# 7DI_V2_R2.net
KiCad netlist of a schematic drawn in EAGLE
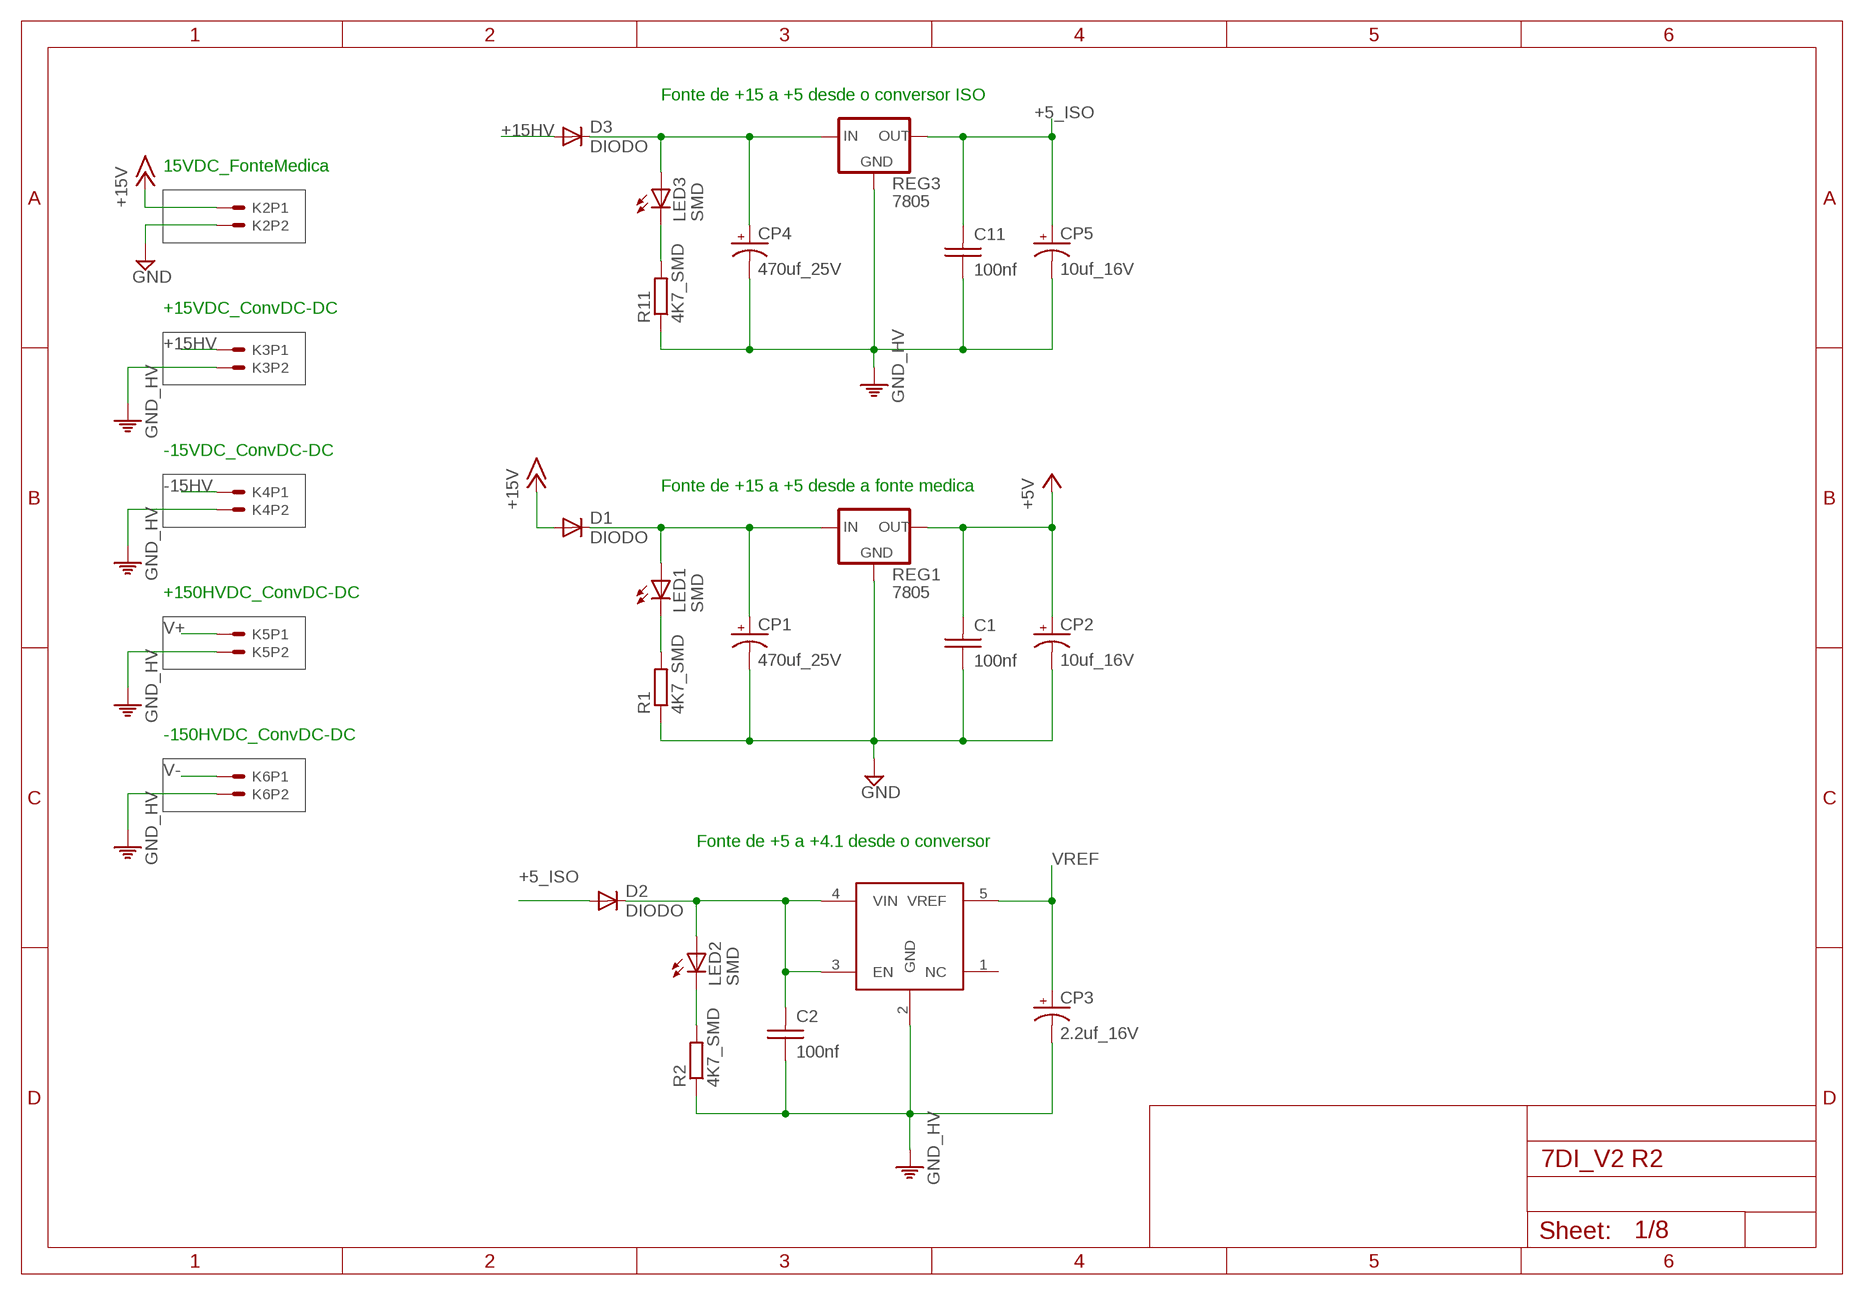
[diagram p0: schematic, sheet 1]
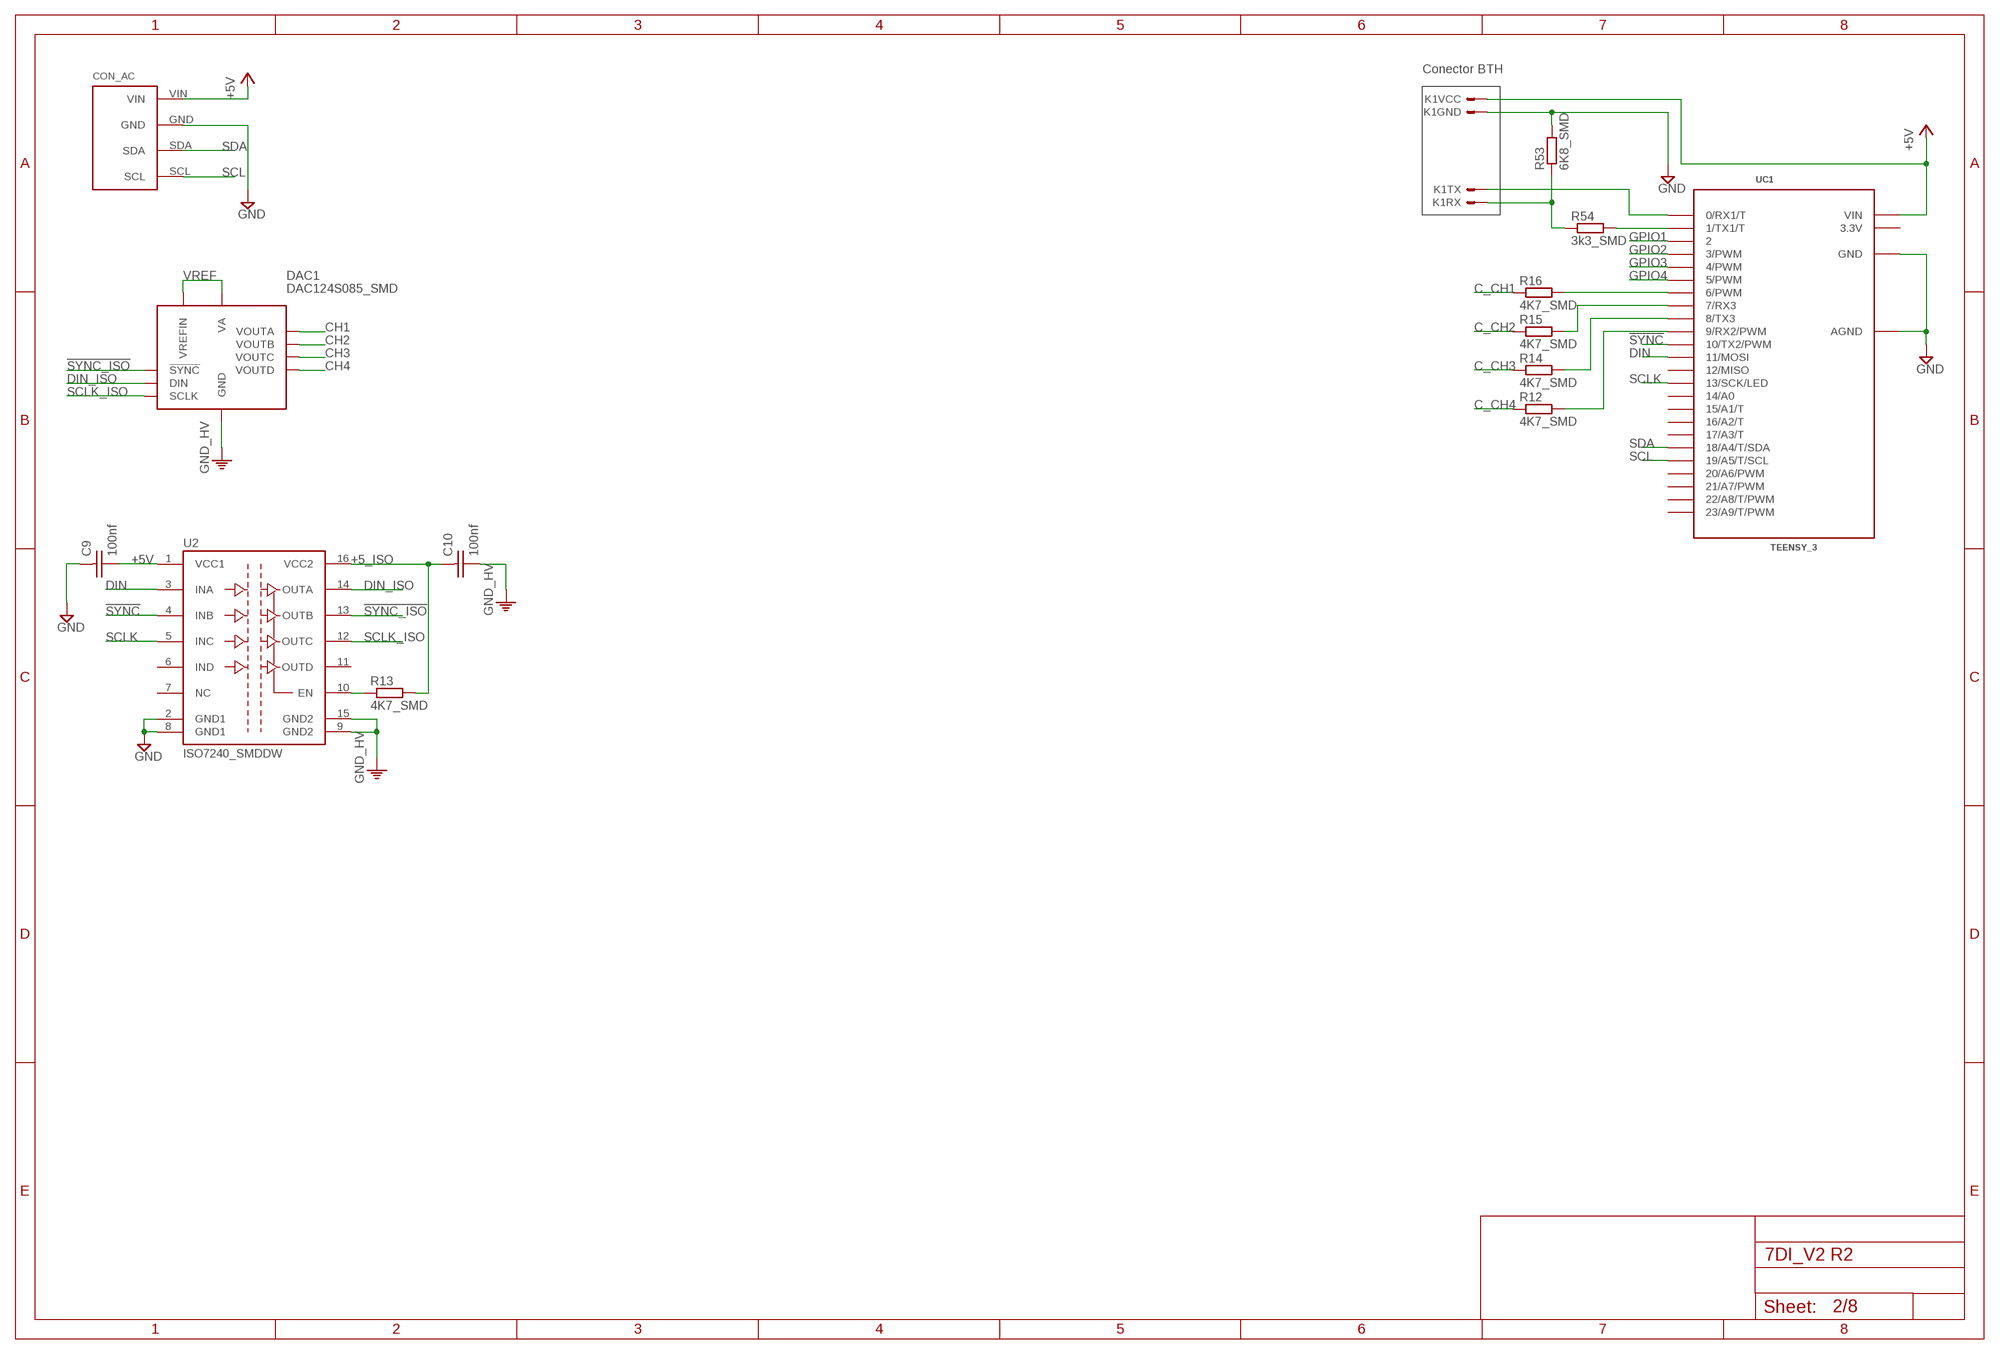
[diagram p1: schematic, sheet 2]
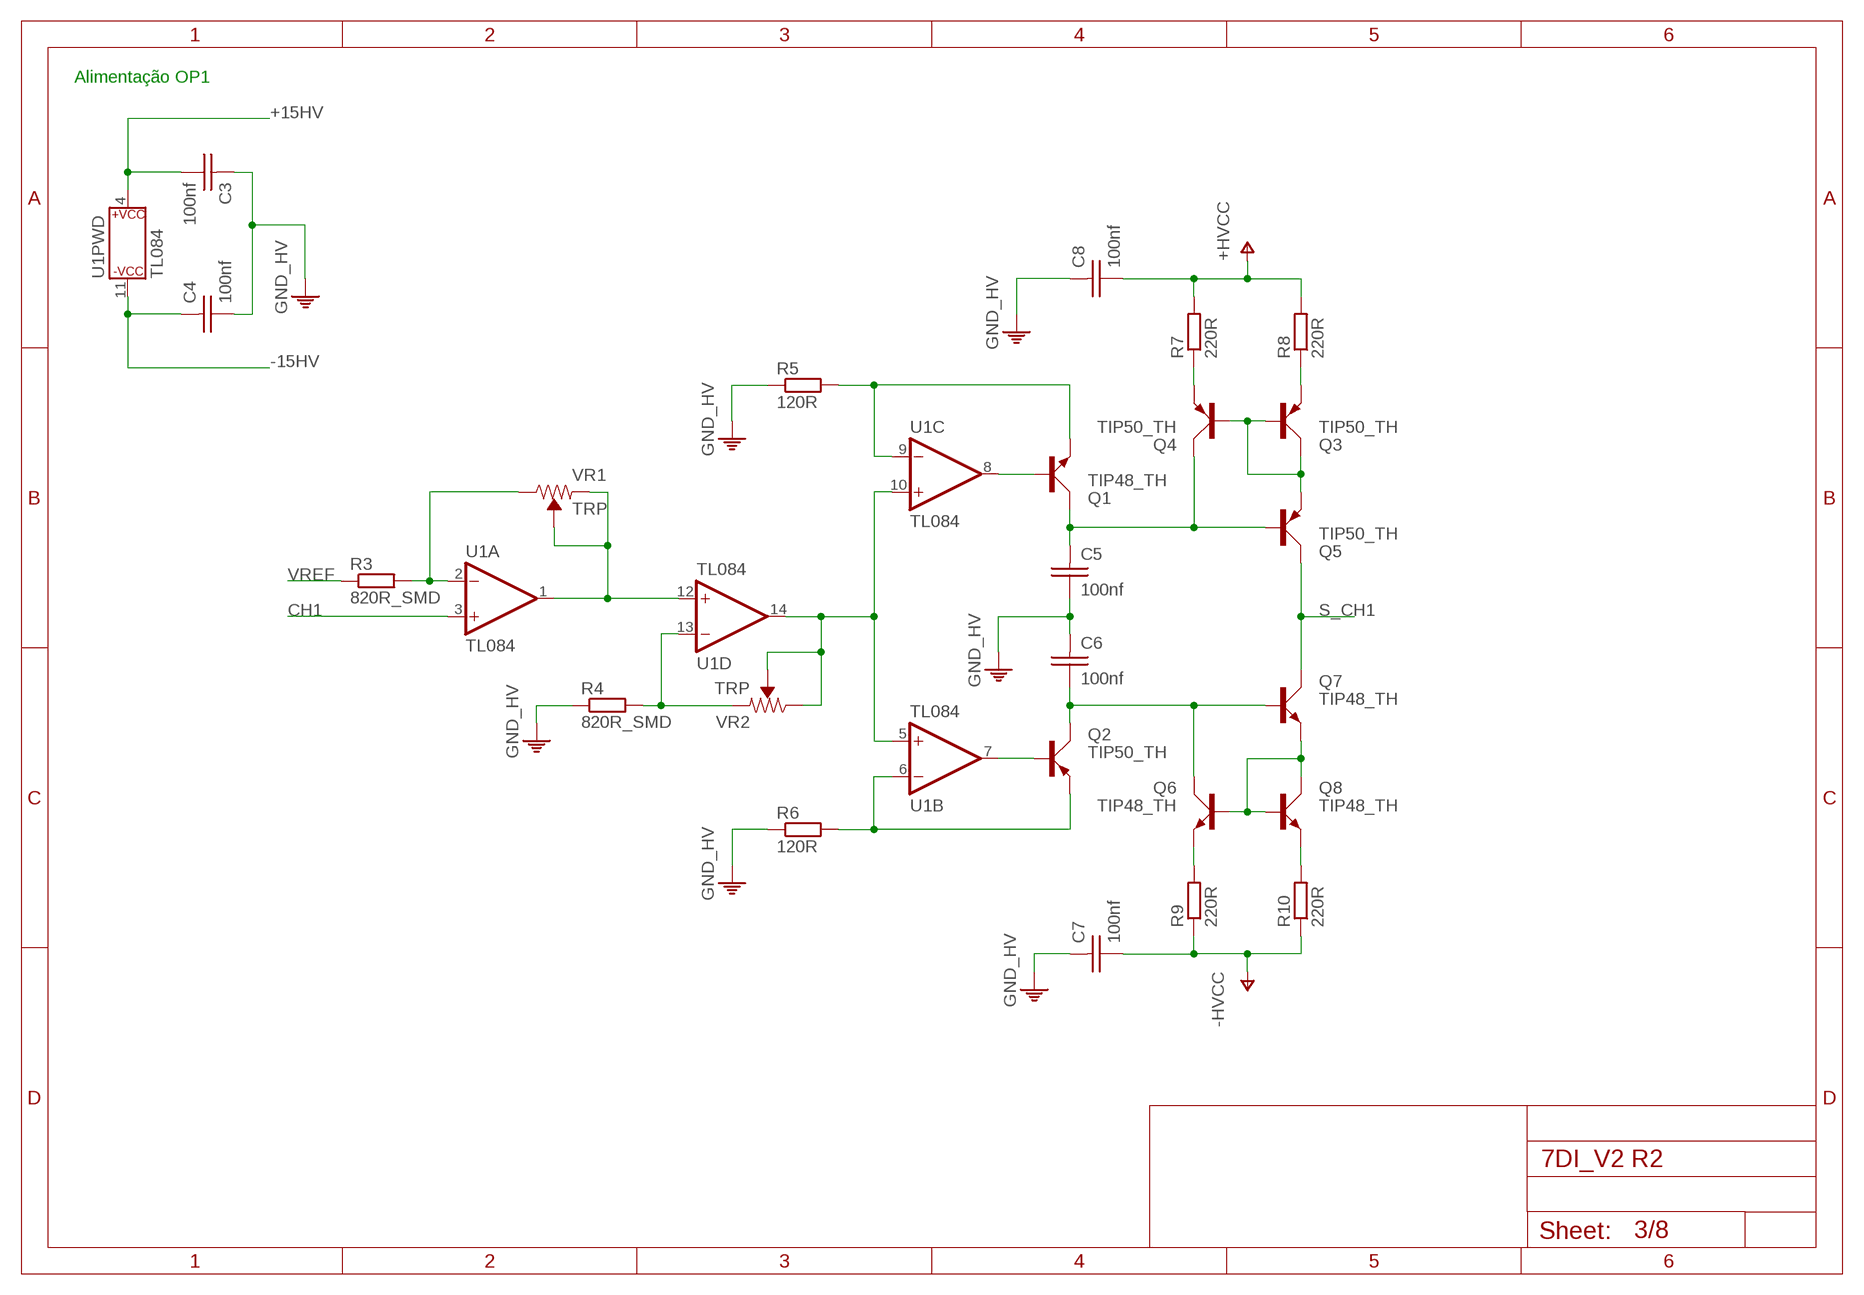
[diagram p2: schematic, sheet 3]
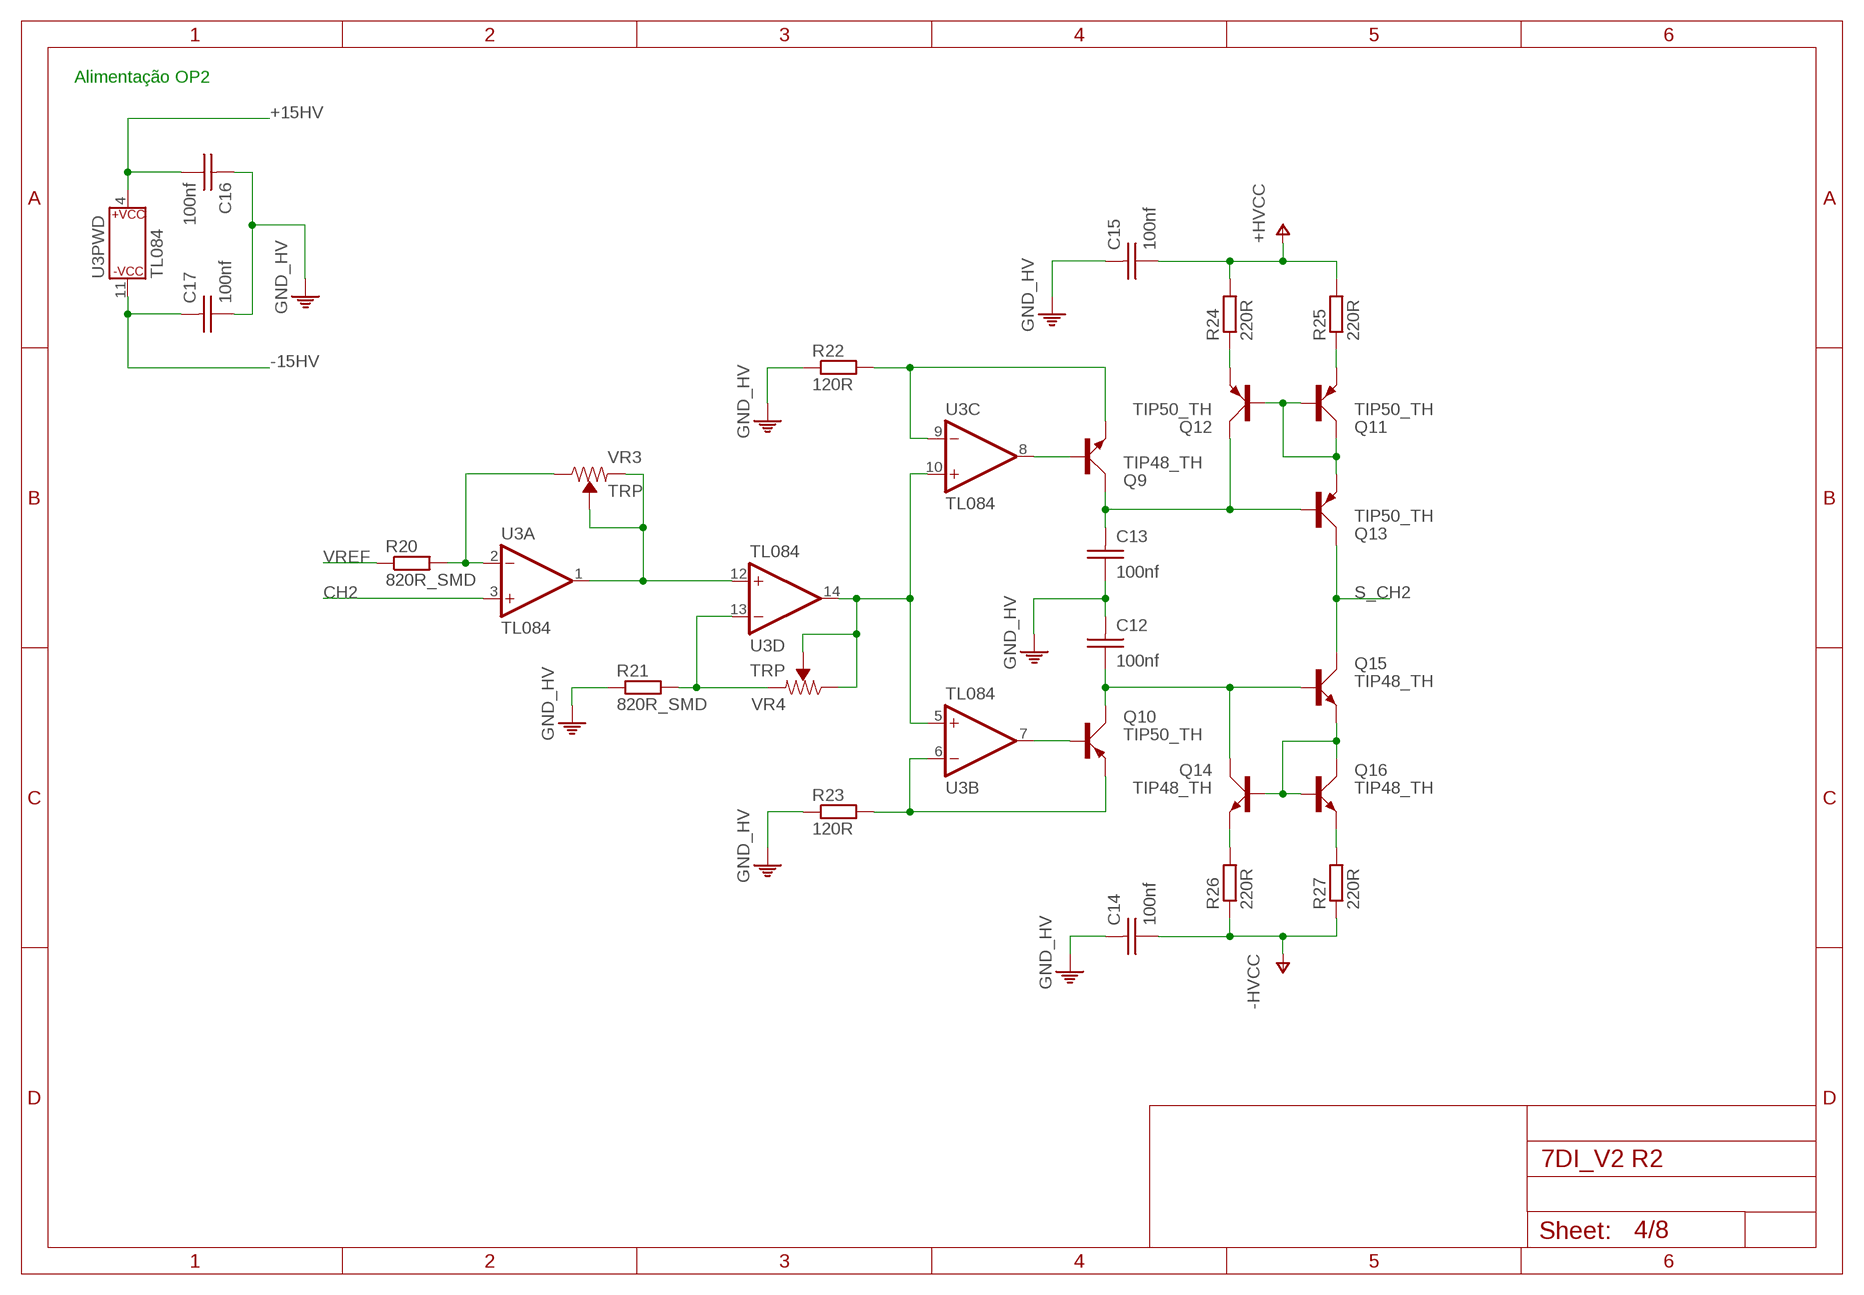
[diagram p3: schematic, sheet 4]
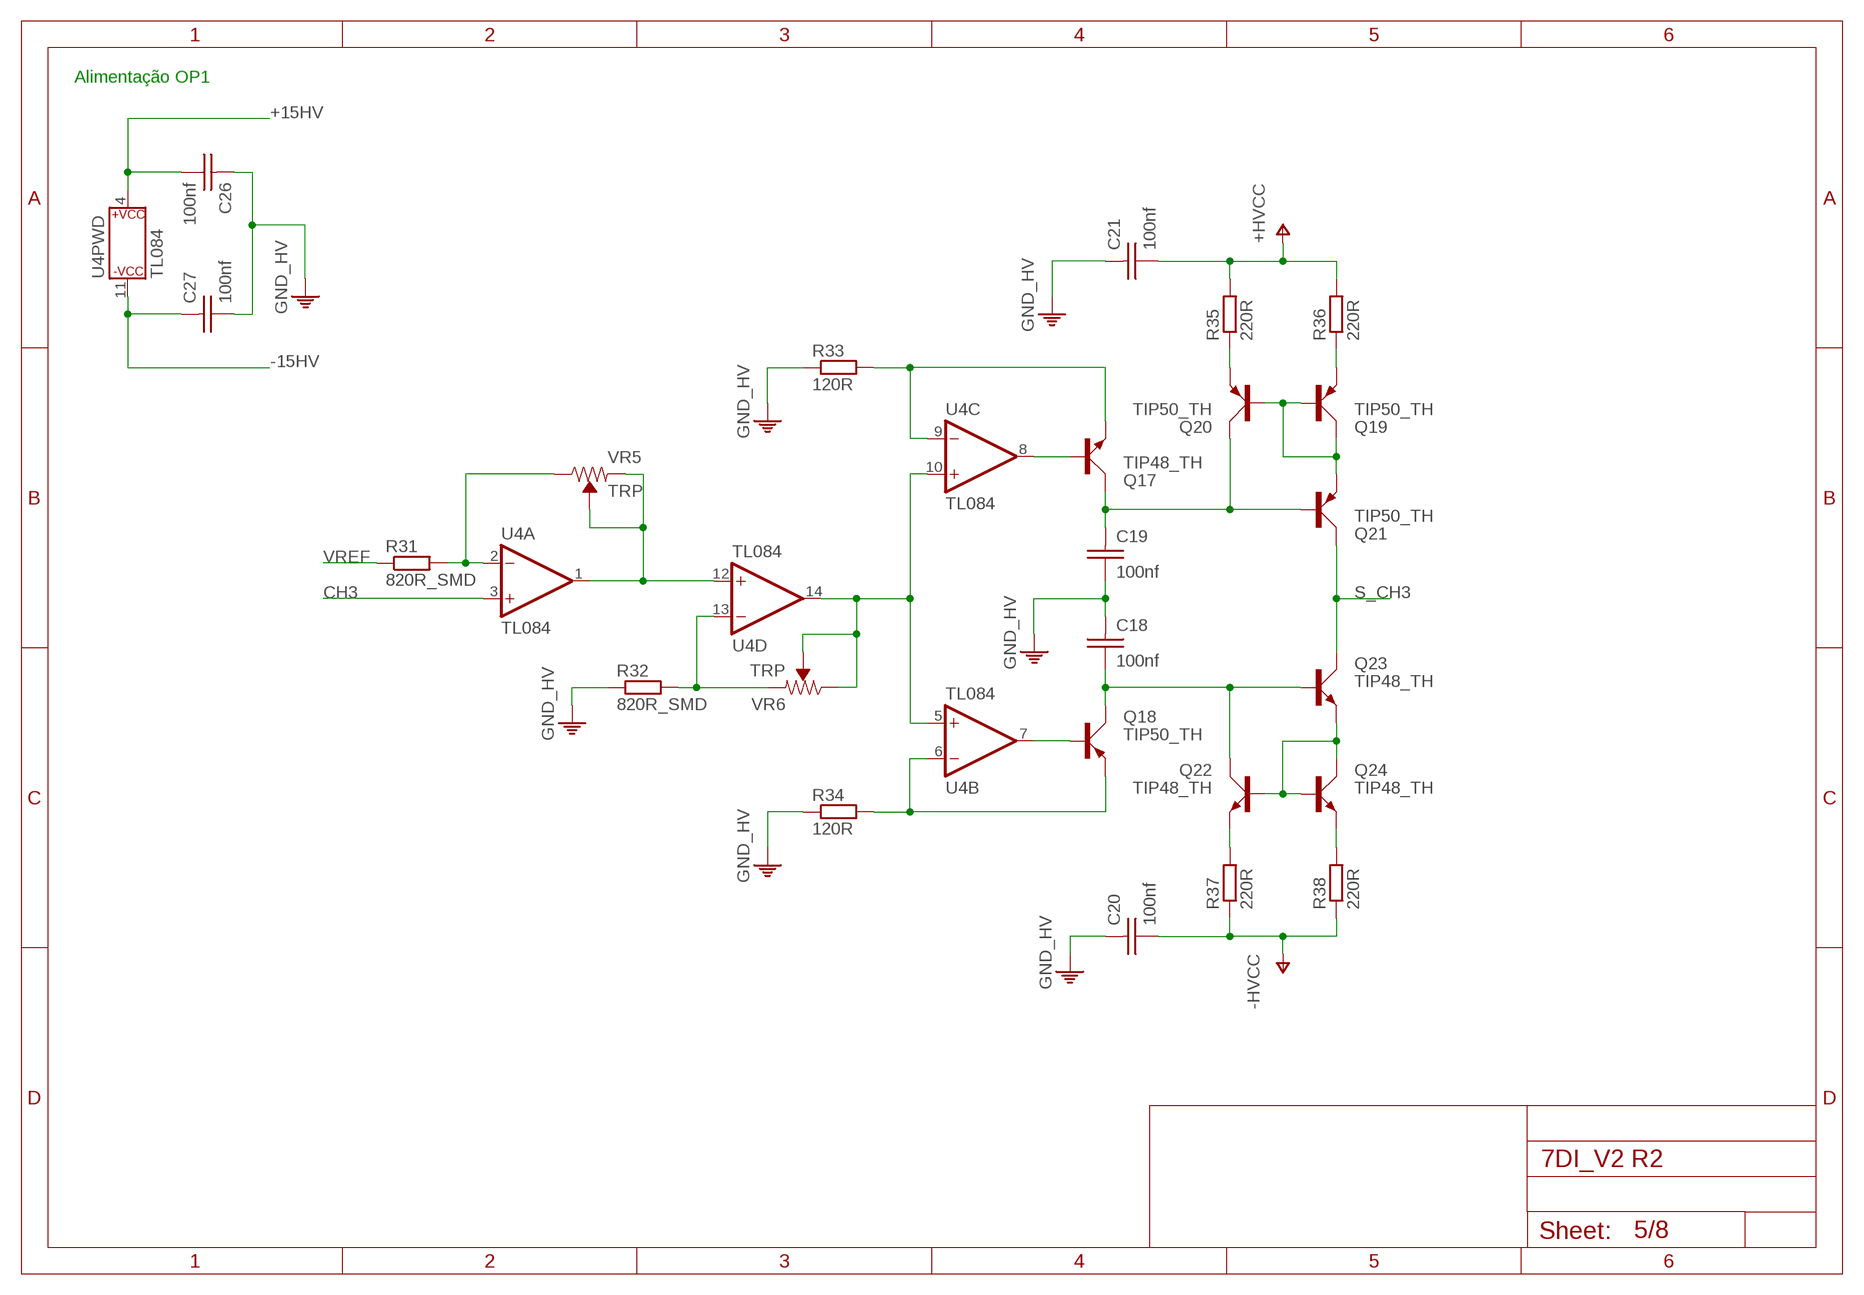
[diagram p4: schematic, sheet 5]
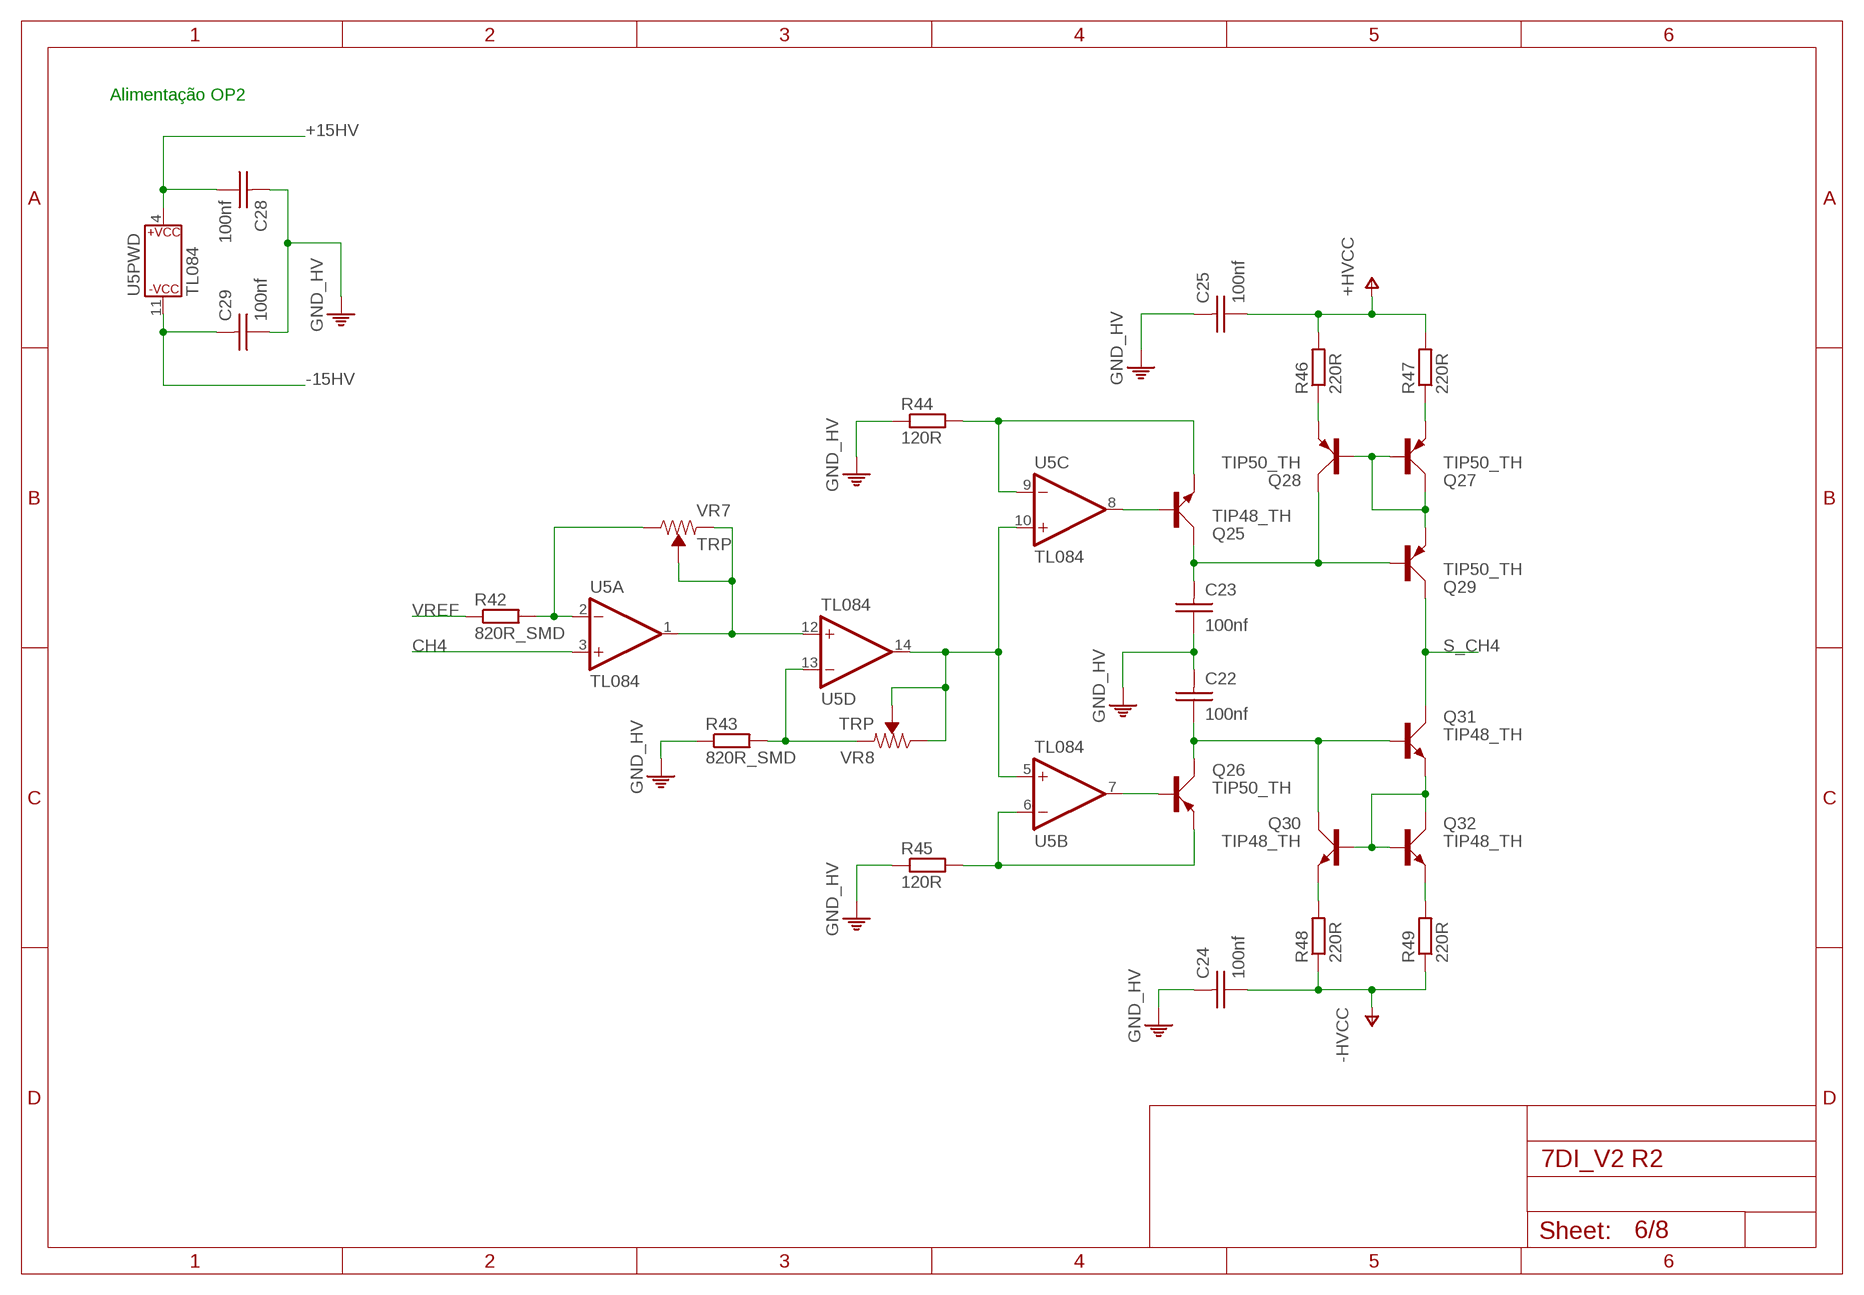
[diagram p5: schematic, sheet 6]
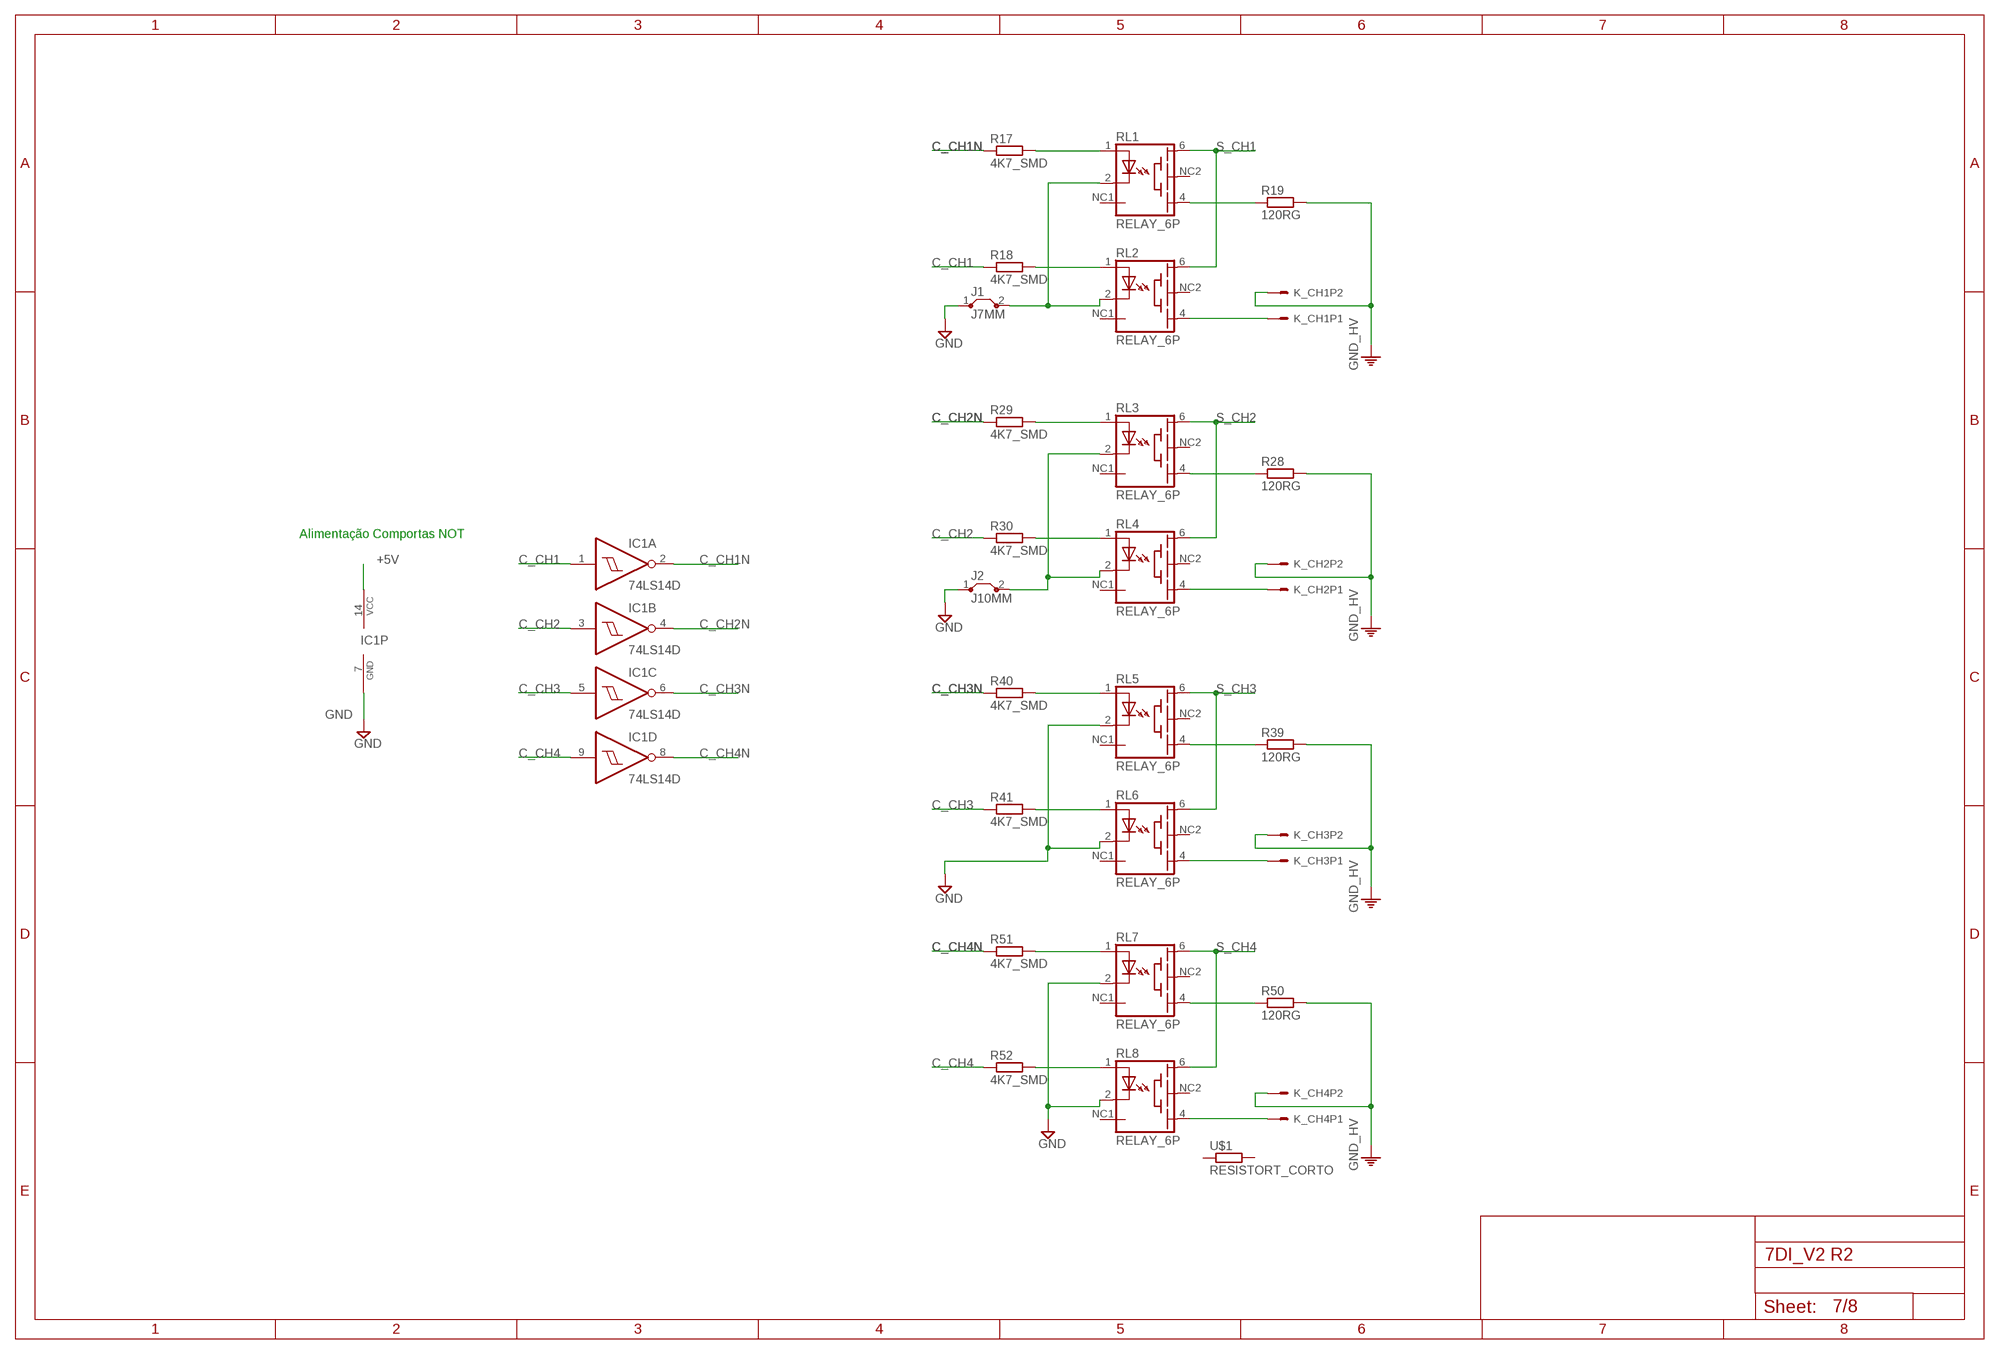
[diagram p6: schematic, sheet 7]
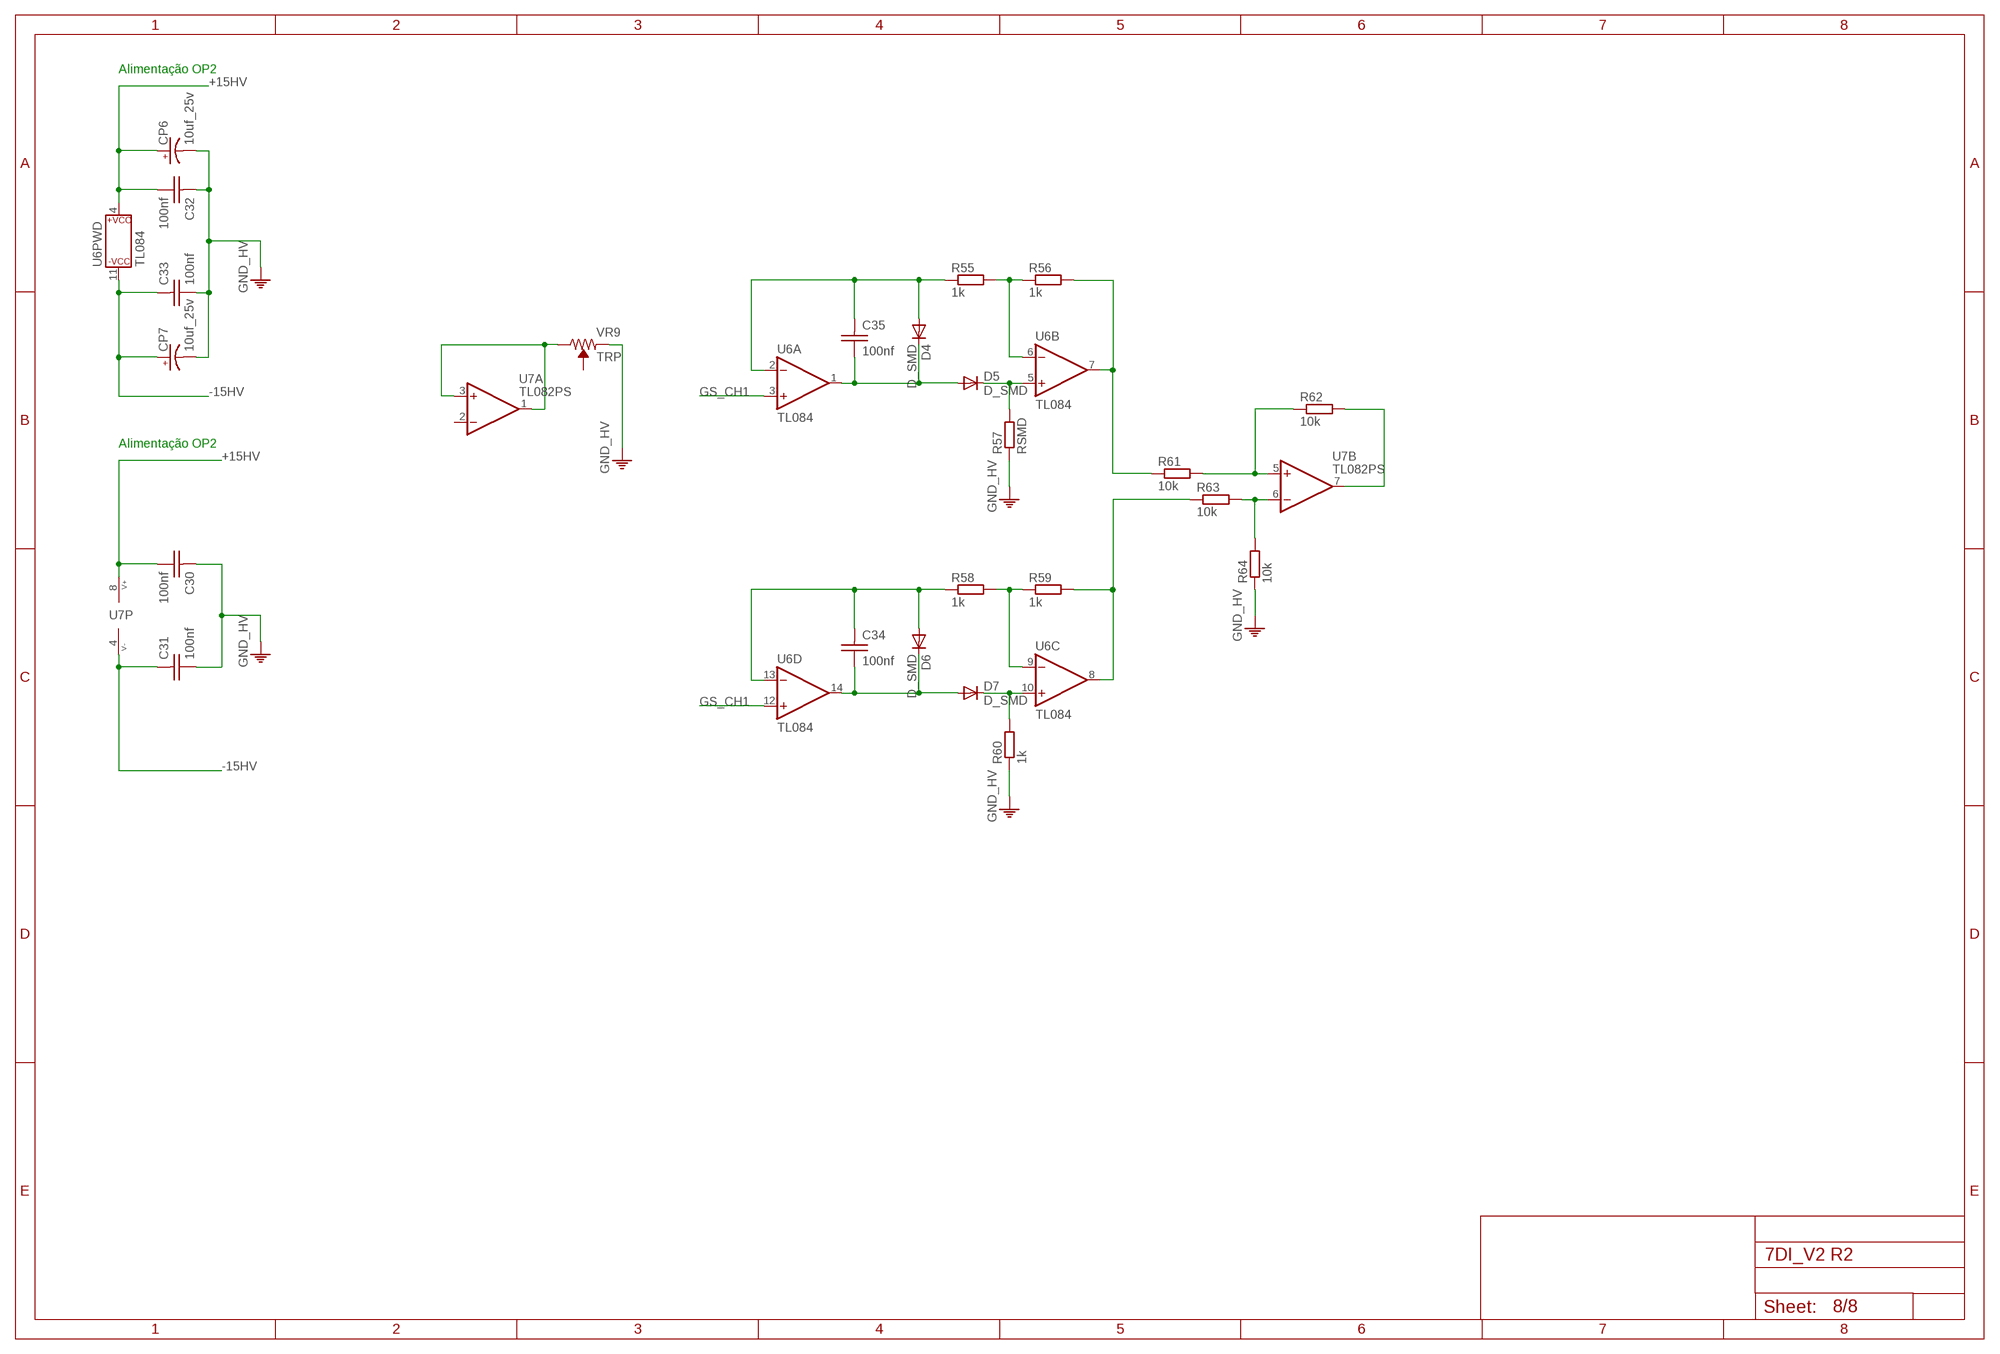
[diagram p7: schematic, sheet 8]

(export (version "E")
  (design (tool "Eeschema 10.0.6"))
  (components
    (comp (ref "C22")
      (value "100nf")
      (footprint "eagle-import:CAP_CER_2,54-5X5")
      (libsource (lib "eagle-import") (part "CAP_CERAMICO_TH2"))
    )
    (comp (ref "C23")
      (value "100nf")
      (footprint "eagle-import:CAP_CER_2,54-5X5")
      (libsource (lib "eagle-import") (part "CAP_CERAMICO_TH2"))
    )
    (comp (ref "C24")
      (value "100nf")
      (footprint "eagle-import:CAP_CER_16X7")
      (libsource (lib "eagle-import") (part "CAP_CERAMICO_TH16"))
    )
    (comp (ref "C25")
      (value "100nf")
      (footprint "eagle-import:CAP_CER_16X7")
      (libsource (lib "eagle-import") (part "CAP_CERAMICO_TH16"))
    )
    (comp (ref "C28")
      (value "100nf")
      (footprint "eagle-import:CAP_CER_SMD-0805")
      (libsource (lib "eagle-import") (part "CAP_CERAMICO_SMD"))
    )
    (comp (ref "C29")
      (value "100nf")
      (footprint "eagle-import:CAP_CER_SMD-0805")
      (libsource (lib "eagle-import") (part "CAP_CERAMICO_SMD"))
    )
    (comp (ref "Q25")
      (value "TIP48_TH")
      (footprint "eagle-import:TO220")
      (libsource (lib "eagle-import") (part "TIP48_TH"))
    )
    (comp (ref "Q26")
      (value "TIP50_TH")
      (footprint "eagle-import:TO220")
      (libsource (lib "eagle-import") (part "TIP50_TH"))
    )
    (comp (ref "Q27")
      (value "TIP50_TH")
      (footprint "eagle-import:TO220")
      (libsource (lib "eagle-import") (part "TIP50_TH"))
    )
    (comp (ref "Q28")
      (value "TIP50_TH")
      (footprint "eagle-import:TO220")
      (libsource (lib "eagle-import") (part "TIP50_TH"))
    )
    (comp (ref "Q29")
      (value "TIP50_TH")
      (footprint "eagle-import:TO220")
      (libsource (lib "eagle-import") (part "TIP50_TH"))
    )
    (comp (ref "Q30")
      (value "TIP48_TH")
      (footprint "eagle-import:TO220")
      (libsource (lib "eagle-import") (part "TIP48_TH"))
    )
    (comp (ref "Q31")
      (value "TIP48_TH")
      (footprint "eagle-import:TO220")
      (libsource (lib "eagle-import") (part "TIP48_TH"))
    )
    (comp (ref "Q32")
      (value "TIP48_TH")
      (footprint "eagle-import:TO220")
      (libsource (lib "eagle-import") (part "TIP48_TH"))
    )
    (comp (ref "R42")
      (value "820R_SMD")
      (footprint "eagle-import:RESISTENCIA_0805")
      (libsource (lib "eagle-import") (part "RESISTORSMD_0805"))
    )
    (comp (ref "R43")
      (value "820R_SMD")
      (footprint "eagle-import:RESISTENCIA_0805")
      (libsource (lib "eagle-import") (part "RESISTORSMD_0805"))
    )
    (comp (ref "R44")
      (value "120R")
      (footprint "eagle-import:0204V")
      (libsource (lib "eagle-import") (part "RESISTORT_CORTO"))
    )
    (comp (ref "R45")
      (value "120R")
      (footprint "eagle-import:0204V")
      (libsource (lib "eagle-import") (part "RESISTORT_CORTO"))
    )
    (comp (ref "R46")
      (value "220R")
      (footprint "eagle-import:0204V")
      (libsource (lib "eagle-import") (part "RESISTORT_CORTO"))
    )
    (comp (ref "R47")
      (value "220R")
      (footprint "eagle-import:0204V")
      (libsource (lib "eagle-import") (part "RESISTORT_CORTO"))
    )
    (comp (ref "R48")
      (value "220R")
      (footprint "eagle-import:0204V")
      (libsource (lib "eagle-import") (part "RESISTORT_CORTO"))
    )
    (comp (ref "R49")
      (value "220R")
      (footprint "eagle-import:0204V")
      (libsource (lib "eagle-import") (part "RESISTORT_CORTO"))
    )
    (comp (ref "U5")
      (value "TL084")
      (footprint "eagle-import:SO14OP")
      (libsource (lib "eagle-import") (part "TL084_SMD"))
    )
    (comp (ref "VR7")
      (value "TRP")
      (footprint "eagle-import:TRIMPOT-PTH-3386U")
      (libsource (lib "eagle-import") (part "TRIMPOT_TH"))
    )
    (comp (ref "VR8")
      (value "TRP")
      (footprint "eagle-import:TRIMPOT-PTH-3386U")
      (libsource (lib "eagle-import") (part "TRIMPOT_TH"))
    )
    (comp (ref "C12")
      (value "100nf")
      (footprint "eagle-import:CAP_CER_2,54-5X5")
      (libsource (lib "eagle-import") (part "CAP_CERAMICO_TH2"))
    )
    (comp (ref "C13")
      (value "100nf")
      (footprint "eagle-import:CAP_CER_2,54-5X5")
      (libsource (lib "eagle-import") (part "CAP_CERAMICO_TH2"))
    )
    (comp (ref "C14")
      (value "100nf")
      (footprint "eagle-import:CAP_CER_16X7")
      (libsource (lib "eagle-import") (part "CAP_CERAMICO_TH16"))
    )
    (comp (ref "C15")
      (value "100nf")
      (footprint "eagle-import:CAP_CER_16X7")
      (libsource (lib "eagle-import") (part "CAP_CERAMICO_TH16"))
    )
    (comp (ref "C16")
      (value "100nf")
      (footprint "eagle-import:CAP_CER_SMD-0805")
      (libsource (lib "eagle-import") (part "CAP_CERAMICO_SMD"))
    )
    (comp (ref "C17")
      (value "100nf")
      (footprint "eagle-import:CAP_CER_SMD-0805")
      (libsource (lib "eagle-import") (part "CAP_CERAMICO_SMD"))
    )
    (comp (ref "Q9")
      (value "TIP48_TH")
      (footprint "eagle-import:TO220")
      (libsource (lib "eagle-import") (part "TIP48_TH"))
    )
    (comp (ref "Q10")
      (value "TIP50_TH")
      (footprint "eagle-import:TO220")
      (libsource (lib "eagle-import") (part "TIP50_TH"))
    )
    (comp (ref "Q11")
      (value "TIP50_TH")
      (footprint "eagle-import:TO220")
      (libsource (lib "eagle-import") (part "TIP50_TH"))
    )
    (comp (ref "Q12")
      (value "TIP50_TH")
      (footprint "eagle-import:TO220")
      (libsource (lib "eagle-import") (part "TIP50_TH"))
    )
    (comp (ref "Q13")
      (value "TIP50_TH")
      (footprint "eagle-import:TO220")
      (libsource (lib "eagle-import") (part "TIP50_TH"))
    )
    (comp (ref "Q14")
      (value "TIP48_TH")
      (footprint "eagle-import:TO220")
      (libsource (lib "eagle-import") (part "TIP48_TH"))
    )
    (comp (ref "Q15")
      (value "TIP48_TH")
      (footprint "eagle-import:TO220")
      (libsource (lib "eagle-import") (part "TIP48_TH"))
    )
    (comp (ref "Q16")
      (value "TIP48_TH")
      (footprint "eagle-import:TO220")
      (libsource (lib "eagle-import") (part "TIP48_TH"))
    )
    (comp (ref "R20")
      (value "820R_SMD")
      (footprint "eagle-import:RESISTENCIA_0805")
      (libsource (lib "eagle-import") (part "RESISTORSMD_0805"))
    )
    (comp (ref "R21")
      (value "820R_SMD")
      (footprint "eagle-import:RESISTENCIA_0805")
      (libsource (lib "eagle-import") (part "RESISTORSMD_0805"))
    )
    (comp (ref "R22")
      (value "120R")
      (footprint "eagle-import:0204V")
      (libsource (lib "eagle-import") (part "RESISTORT_CORTO"))
    )
    (comp (ref "R23")
      (value "120R")
      (footprint "eagle-import:0204V")
      (libsource (lib "eagle-import") (part "RESISTORT_CORTO"))
    )
    (comp (ref "R24")
      (value "220R")
      (footprint "eagle-import:0204V")
      (libsource (lib "eagle-import") (part "RESISTORT_CORTO"))
    )
    (comp (ref "R25")
      (value "220R")
      (footprint "eagle-import:0204V")
      (libsource (lib "eagle-import") (part "RESISTORT_CORTO"))
    )
    (comp (ref "R26")
      (value "220R")
      (footprint "eagle-import:0204V")
      (libsource (lib "eagle-import") (part "RESISTORT_CORTO"))
    )
    (comp (ref "R27")
      (value "220R")
      (footprint "eagle-import:0204V")
      (libsource (lib "eagle-import") (part "RESISTORT_CORTO"))
    )
    (comp (ref "U3")
      (value "TL084")
      (footprint "eagle-import:SO14OP")
      (libsource (lib "eagle-import") (part "TL084_SMD"))
    )
    (comp (ref "VR3")
      (value "TRP")
      (footprint "eagle-import:TRIMPOT-PTH-3386U")
      (libsource (lib "eagle-import") (part "TRIMPOT_TH"))
    )
    (comp (ref "VR4")
      (value "TRP")
      (footprint "eagle-import:TRIMPOT-PTH-3386U")
      (libsource (lib "eagle-import") (part "TRIMPOT_TH"))
    )
    (comp (ref "C3")
      (value "100nf")
      (footprint "eagle-import:CAP_CER_SMD-0805")
      (libsource (lib "eagle-import") (part "CAP_CERAMICO_SMD"))
    )
    (comp (ref "C4")
      (value "100nf")
      (footprint "eagle-import:CAP_CER_SMD-0805")
      (libsource (lib "eagle-import") (part "CAP_CERAMICO_SMD"))
    )
    (comp (ref "C5")
      (value "100nf")
      (footprint "eagle-import:CAP_CER_2,54-5X5")
      (libsource (lib "eagle-import") (part "CAP_CERAMICO_TH2"))
    )
    (comp (ref "C6")
      (value "100nf")
      (footprint "eagle-import:CAP_CER_2,54-5X5")
      (libsource (lib "eagle-import") (part "CAP_CERAMICO_TH2"))
    )
    (comp (ref "C7")
      (value "100nf")
      (footprint "eagle-import:CAP_CER_16X7")
      (libsource (lib "eagle-import") (part "CAP_CERAMICO_TH16"))
    )
    (comp (ref "C8")
      (value "100nf")
      (footprint "eagle-import:CAP_CER_16X7")
      (libsource (lib "eagle-import") (part "CAP_CERAMICO_TH16"))
    )
    (comp (ref "Q1")
      (value "TIP48_TH")
      (footprint "eagle-import:TO220")
      (libsource (lib "eagle-import") (part "TIP48_TH"))
    )
    (comp (ref "Q2")
      (value "TIP50_TH")
      (footprint "eagle-import:TO220")
      (libsource (lib "eagle-import") (part "TIP50_TH"))
    )
    (comp (ref "Q3")
      (value "TIP50_TH")
      (footprint "eagle-import:TO220")
      (libsource (lib "eagle-import") (part "TIP50_TH"))
    )
    (comp (ref "Q4")
      (value "TIP50_TH")
      (footprint "eagle-import:TO220")
      (libsource (lib "eagle-import") (part "TIP50_TH"))
    )
    (comp (ref "Q5")
      (value "TIP50_TH")
      (footprint "eagle-import:TO220")
      (libsource (lib "eagle-import") (part "TIP50_TH"))
    )
    (comp (ref "Q6")
      (value "TIP48_TH")
      (footprint "eagle-import:TO220")
      (libsource (lib "eagle-import") (part "TIP48_TH"))
    )
    (comp (ref "Q7")
      (value "TIP48_TH")
      (footprint "eagle-import:TO220")
      (libsource (lib "eagle-import") (part "TIP48_TH"))
    )
    (comp (ref "Q8")
      (value "TIP48_TH")
      (footprint "eagle-import:TO220")
      (libsource (lib "eagle-import") (part "TIP48_TH"))
    )
    (comp (ref "R3")
      (value "820R_SMD")
      (footprint "eagle-import:RESISTENCIA_0805")
      (libsource (lib "eagle-import") (part "RESISTORSMD_0805"))
    )
    (comp (ref "R4")
      (value "820R_SMD")
      (footprint "eagle-import:RESISTENCIA_0805")
      (libsource (lib "eagle-import") (part "RESISTORSMD_0805"))
    )
    (comp (ref "R5")
      (value "120R")
      (footprint "eagle-import:0204V")
      (libsource (lib "eagle-import") (part "RESISTORT_CORTO"))
    )
    (comp (ref "R6")
      (value "120R")
      (footprint "eagle-import:0204V")
      (libsource (lib "eagle-import") (part "RESISTORT_CORTO"))
    )
    (comp (ref "R7")
      (value "220R")
      (footprint "eagle-import:0204V")
      (libsource (lib "eagle-import") (part "RESISTORT_CORTO"))
    )
    (comp (ref "R8")
      (value "220R")
      (footprint "eagle-import:0204V")
      (libsource (lib "eagle-import") (part "RESISTORT_CORTO"))
    )
    (comp (ref "R9")
      (value "220R")
      (footprint "eagle-import:0204V")
      (libsource (lib "eagle-import") (part "RESISTORT_CORTO"))
    )
    (comp (ref "R10")
      (value "220R")
      (footprint "eagle-import:0204V")
      (libsource (lib "eagle-import") (part "RESISTORT_CORTO"))
    )
    (comp (ref "U1")
      (value "TL084")
      (footprint "eagle-import:SO14OP")
      (libsource (lib "eagle-import") (part "TL084_SMD"))
    )
    (comp (ref "VR1")
      (value "TRP")
      (footprint "eagle-import:TRIMPOT-PTH-3386U")
      (libsource (lib "eagle-import") (part "TRIMPOT_TH"))
    )
    (comp (ref "VR2")
      (value "TRP")
      (footprint "eagle-import:TRIMPOT-PTH-3386U")
      (libsource (lib "eagle-import") (part "TRIMPOT_TH"))
    )
    (comp (ref "C1")
      (value "100nf")
      (footprint "eagle-import:CAP_CER_5,08-024X044")
      (libsource (lib "eagle-import") (part "CAP_CERAMICO_TH5"))
    )
    (comp (ref "C2")
      (value "100nf")
      (footprint "eagle-import:CAP_CER_SMD-0805")
      (libsource (lib "eagle-import") (part "CAP_CERAMICO_SMD"))
    )
    (comp (ref "C11")
      (value "100nf")
      (footprint "eagle-import:CAP_CER_5,08-024X044")
      (libsource (lib "eagle-import") (part "CAP_CERAMICO_TH5"))
    )
    (comp (ref "CP1")
      (value "470uf_25V")
      (footprint "eagle-import:CAP_T_3,5-D8")
      (libsource (lib "eagle-import") (part "CAP_POLARIZADOCAP_T3,5-D8"))
    )
    (comp (ref "CP2")
      (value "10uf_16V")
      (footprint "eagle-import:CAP_T_2,5-D5")
      (libsource (lib "eagle-import") (part "CAP_POLARIZADOCAP_T2,5-D5"))
    )
    (comp (ref "CP3")
      (value "2.2uf_16V")
      (footprint "eagle-import:153CLV-0605")
      (libsource (lib "eagle-import") (part "CAP_POLARIZADOCAPDAC"))
    )
    (comp (ref "CP4")
      (value "470uf_25V")
      (footprint "eagle-import:CAP_T_3,5-D8")
      (libsource (lib "eagle-import") (part "CAP_POLARIZADOCAP_T3,5-D8"))
    )
    (comp (ref "CP5")
      (value "10uf_16V")
      (footprint "eagle-import:CAP_T_2,5-D5")
      (libsource (lib "eagle-import") (part "CAP_POLARIZADOCAP_T2,5-D5"))
    )
    (comp (ref "D1")
      (value "DIODO")
      (footprint "eagle-import:D-5")
      (libsource (lib "eagle-import") (part "DIODOT_5"))
    )
    (comp (ref "D2")
      (value "DIODO")
      (footprint "eagle-import:D-5")
      (libsource (lib "eagle-import") (part "DIODOT_5"))
    )
    (comp (ref "D3")
      (value "DIODO")
      (footprint "eagle-import:D-5")
      (libsource (lib "eagle-import") (part "DIODOT_5"))
    )
    (comp (ref "K2")
      (value "CONECTOR_5.08")
      (footprint "eagle-import:CONECTOR_X2_5.08")
      (fields (field (name "SPICEPREFIX") "X"))
      (libsource (lib "eagle-import") (part "CONECTOR_5.08"))
    )
    (comp (ref "K3")
      (value "vcc")
      (footprint "eagle-import:CONECTOR_X2_5.08")
      (libsource (lib "eagle-import") (part "CONECTOR_5.08"))
    )
    (comp (ref "K4")
      (value "vcc")
      (footprint "eagle-import:CONECTOR_X2_5.08")
      (libsource (lib "eagle-import") (part "CONECTOR_5.08"))
    )
    (comp (ref "K5")
      (value "vcc")
      (footprint "eagle-import:CONECTOR_X2_5.08")
      (libsource (lib "eagle-import") (part "CONECTOR_5.08"))
    )
    (comp (ref "K6")
      (value "vcc")
      (footprint "eagle-import:CONECTOR_X2_5.08")
      (libsource (lib "eagle-import") (part "CONECTOR_5.08"))
    )
    (comp (ref "LED1")
      (value "SMD")
      (footprint "eagle-import:LED_0805")
      (libsource (lib "eagle-import") (part "LEDSMD_0805"))
    )
    (comp (ref "LED2")
      (value "SMD")
      (footprint "eagle-import:LED_0805")
      (libsource (lib "eagle-import") (part "LEDSMD_0805"))
    )
    (comp (ref "LED3")
      (value "SMD")
      (footprint "eagle-import:LED_0805")
      (libsource (lib "eagle-import") (part "LEDSMD_0805"))
    )
    (comp (ref "R1")
      (value "4K7_SMD")
      (footprint "eagle-import:RESISTENCIA_0805")
      (libsource (lib "eagle-import") (part "RESISTORSMD_0805"))
    )
    (comp (ref "R2")
      (value "4K7_SMD")
      (footprint "eagle-import:RESISTENCIA_0805")
      (libsource (lib "eagle-import") (part "RESISTORSMD_0805"))
    )
    (comp (ref "R11")
      (value "4K7_SMD")
      (footprint "eagle-import:RESISTENCIA_0805")
      (libsource (lib "eagle-import") (part "RESISTORSMD_0805"))
    )
    (comp (ref "REG1")
      (value "7805")
      (footprint "eagle-import:78XXS")
      (libsource (lib "eagle-import") (part "REGULADOR_78XX"))
    )
    (comp (ref "REG2")
      (value "lm4132_4.1")
      (footprint "eagle-import:SOT23")
      (libsource (lib "eagle-import") (part "REGULADOR_LM4132_4.1_SMDREGULADOR_ALTA_PRECISION"))
    )
    (comp (ref "REG3")
      (value "7805")
      (footprint "eagle-import:78XXS")
      (libsource (lib "eagle-import") (part "REGULADOR_78XX"))
    )
    (comp (ref "C9")
      (value "100nf")
      (footprint "eagle-import:CAP_CER_SMD-0805")
      (libsource (lib "eagle-import") (part "CAP_CERAMICO_SMD"))
    )
    (comp (ref "C10")
      (value "100nf")
      (footprint "eagle-import:CAP_CER_SMD-0805")
      (libsource (lib "eagle-import") (part "CAP_CERAMICO_SMD"))
    )
    (comp (ref "CON_AC")
      (value "CON_MPU6050")
      (footprint "eagle-import:MPU6050")
      (libsource (lib "eagle-import") (part "CONECTOR_ACELEROMETRO_MPU6050CONECTOR_MPU6050"))
    )
    (comp (ref "DAC1")
      (value "DAC124S085_SMD")
      (footprint "eagle-import:DAC_SO10")
      (libsource (lib "eagle-import") (part "DAC124S085_SMD"))
    )
    (comp (ref "K1")
      (value "CONECTOR_BTHC-06HC-06")
      (footprint "eagle-import:CONECTOR_BTHC-06")
      (libsource (lib "eagle-import") (part "CONECTOR_BTHC-06HC-06"))
    )
    (comp (ref "R12")
      (value "4K7_SMD")
      (footprint "eagle-import:RESISTENCIA_0805")
      (libsource (lib "eagle-import") (part "RESISTORSMD_0805"))
    )
    (comp (ref "R13")
      (value "4K7_SMD")
      (footprint "eagle-import:RESISTENCIA_0805")
      (libsource (lib "eagle-import") (part "RESISTORSMD_0805"))
    )
    (comp (ref "R14")
      (value "4K7_SMD")
      (footprint "eagle-import:RESISTENCIA_0805")
      (libsource (lib "eagle-import") (part "RESISTORSMD_0805"))
    )
    (comp (ref "R15")
      (value "4K7_SMD")
      (footprint "eagle-import:RESISTENCIA_0805")
      (libsource (lib "eagle-import") (part "RESISTORSMD_0805"))
    )
    (comp (ref "R16")
      (value "4K7_SMD")
      (footprint "eagle-import:RESISTENCIA_0805")
      (libsource (lib "eagle-import") (part "RESISTORSMD_0805"))
    )
    (comp (ref "R53")
      (value "6K8_SMD")
      (footprint "eagle-import:RESISTENCIA_0805")
      (libsource (lib "eagle-import") (part "RESISTORSMD_0805"))
    )
    (comp (ref "R54")
      (value "3k3_SMD")
      (footprint "eagle-import:RESISTENCIA_0805")
      (libsource (lib "eagle-import") (part "RESISTORSMD_0805"))
    )
    (comp (ref "U2")
      (value "ISO7240_SMDDW")
      (footprint "eagle-import:SO-16DW")
      (libsource (lib "eagle-import") (part "ISO7240_SMDDW"))
    )
    (comp (ref "UC1")
      (value "TEENSY_3")
      (footprint "eagle-import:TEENSY_3.0-3.2_DIL")
      (libsource (lib "eagle-import") (part "TEENSY_3.0_A_3.2VERSION_MINIMA"))
    )
    (comp (ref "IC1")
      (value "74LS14D")
      (footprint "eagle-import:SO14NOT")
      (libsource (lib "eagle-import") (part "7414DLS"))
    )
    (comp (ref "J1")
      (value "J7MM")
      (footprint "eagle-import:07")
      (libsource (lib "eagle-import") (part "J7MM"))
    )
    (comp (ref "J2")
      (value "J10MM")
      (footprint "eagle-import:10")
      (libsource (lib "eagle-import") (part "J10MM"))
    )
    (comp (ref "K_CH1")
      (value "CONECTOR_5.08")
      (footprint "eagle-import:CONECTOR_X2_5.08")
      (libsource (lib "eagle-import") (part "CONECTOR_5.08"))
    )
    (comp (ref "K_CH2")
      (value "CONECTOR_5.08")
      (footprint "eagle-import:CONECTOR_X2_5.08")
      (libsource (lib "eagle-import") (part "CONECTOR_5.08"))
    )
    (comp (ref "K_CH3")
      (value "CONECTOR_5.08")
      (footprint "eagle-import:CONECTOR_X2_5.08")
      (libsource (lib "eagle-import") (part "CONECTOR_5.08"))
    )
    (comp (ref "K_CH4")
      (value "CONECTOR_5.08")
      (footprint "eagle-import:CONECTOR_X2_5.08")
      (libsource (lib "eagle-import") (part "CONECTOR_5.08"))
    )
    (comp (ref "R17")
      (value "4K7_SMD")
      (footprint "eagle-import:RESISTENCIA_0805")
      (libsource (lib "eagle-import") (part "RESISTORSMD_0805"))
    )
    (comp (ref "R18")
      (value "4K7_SMD")
      (footprint "eagle-import:RESISTENCIA_0805")
      (libsource (lib "eagle-import") (part "RESISTORSMD_0805"))
    )
    (comp (ref "R19")
      (value "120RG")
      (footprint "eagle-import:0617V")
      (libsource (lib "eagle-import") (part "RESISTORT_GRANDE"))
    )
    (comp (ref "R28")
      (value "120RG")
      (footprint "eagle-import:0617V")
      (libsource (lib "eagle-import") (part "RESISTORT_GRANDE"))
    )
    (comp (ref "R29")
      (value "4K7_SMD")
      (footprint "eagle-import:RESISTENCIA_0805")
      (libsource (lib "eagle-import") (part "RESISTORSMD_0805"))
    )
    (comp (ref "R30")
      (value "4K7_SMD")
      (footprint "eagle-import:RESISTENCIA_0805")
      (libsource (lib "eagle-import") (part "RESISTORSMD_0805"))
    )
    (comp (ref "R39")
      (value "120RG")
      (footprint "eagle-import:0617V")
      (libsource (lib "eagle-import") (part "RESISTORT_GRANDE"))
    )
    (comp (ref "R40")
      (value "4K7_SMD")
      (footprint "eagle-import:RESISTENCIA_0805")
      (libsource (lib "eagle-import") (part "RESISTORSMD_0805"))
    )
    (comp (ref "R41")
      (value "4K7_SMD")
      (footprint "eagle-import:RESISTENCIA_0805")
      (libsource (lib "eagle-import") (part "RESISTORSMD_0805"))
    )
    (comp (ref "R50")
      (value "120RG")
      (footprint "eagle-import:0617V")
      (libsource (lib "eagle-import") (part "RESISTORT_GRANDE"))
    )
    (comp (ref "R51")
      (value "4K7_SMD")
      (footprint "eagle-import:RESISTENCIA_0805")
      (libsource (lib "eagle-import") (part "RESISTORSMD_0805"))
    )
    (comp (ref "R52")
      (value "4K7_SMD")
      (footprint "eagle-import:RESISTENCIA_0805")
      (libsource (lib "eagle-import") (part "RESISTORSMD_0805"))
    )
    (comp (ref "RL1")
      (value "RELAY_6P")
      (footprint "eagle-import:TS210")
      (libsource (lib "eagle-import") (part "RELAY_6P"))
    )
    (comp (ref "RL2")
      (value "RELAY_6P")
      (footprint "eagle-import:TS210")
      (libsource (lib "eagle-import") (part "RELAY_6P"))
    )
    (comp (ref "RL3")
      (value "RELAY_6P")
      (footprint "eagle-import:TS210")
      (libsource (lib "eagle-import") (part "RELAY_6P"))
    )
    (comp (ref "RL4")
      (value "RELAY_6P")
      (footprint "eagle-import:TS210")
      (libsource (lib "eagle-import") (part "RELAY_6P"))
    )
    (comp (ref "RL5")
      (value "RELAY_6P")
      (footprint "eagle-import:TS210")
      (libsource (lib "eagle-import") (part "RELAY_6P"))
    )
    (comp (ref "RL6")
      (value "RELAY_6P")
      (footprint "eagle-import:TS210")
      (libsource (lib "eagle-import") (part "RELAY_6P"))
    )
    (comp (ref "RL7")
      (value "RELAY_6P")
      (footprint "eagle-import:TS210")
      (libsource (lib "eagle-import") (part "RELAY_6P"))
    )
    (comp (ref "RL8")
      (value "RELAY_6P")
      (footprint "eagle-import:TS210")
      (libsource (lib "eagle-import") (part "RELAY_6P"))
    )
    (comp (ref "U$1")
      (value "RESISTORT_CORTO")
      (footprint "eagle-import:0204V")
      (libsource (lib "eagle-import") (part "RESISTORT_CORTO"))
    )
    (comp (ref "C30")
      (value "100nf")
      (footprint "eagle-import:CAP_CER_SMD-0805")
      (libsource (lib "eagle-import") (part "CAP_CERAMICO_SMD"))
    )
    (comp (ref "C31")
      (value "100nf")
      (footprint "eagle-import:CAP_CER_SMD-0805")
      (libsource (lib "eagle-import") (part "CAP_CERAMICO_SMD"))
    )
    (comp (ref "C32")
      (value "100nf")
      (footprint "eagle-import:CAP_CER_SMD-0805")
      (libsource (lib "eagle-import") (part "CAP_CERAMICO_SMD"))
    )
    (comp (ref "C33")
      (value "100nf")
      (footprint "eagle-import:CAP_CER_SMD-0805")
      (libsource (lib "eagle-import") (part "CAP_CERAMICO_SMD"))
    )
    (comp (ref "C34")
      (value "100nf")
      (footprint "eagle-import:CAP_CER_SMD-0805")
      (libsource (lib "eagle-import") (part "CAP_CERAMICO_SMD"))
    )
    (comp (ref "C35")
      (value "100nf")
      (footprint "eagle-import:CAP_CER_SMD-0805")
      (libsource (lib "eagle-import") (part "CAP_CERAMICO_SMD"))
    )
    (comp (ref "CP6")
      (value "10uf_25v")
      (footprint "eagle-import:CAP_T_2,5-D5")
      (libsource (lib "eagle-import") (part "CAP_POLARIZADOCAP_T2,5-D5"))
    )
    (comp (ref "CP7")
      (value "10uf_25v")
      (footprint "eagle-import:CAP_T_2,5-D5")
      (libsource (lib "eagle-import") (part "CAP_POLARIZADOCAP_T2,5-D5"))
    )
    (comp (ref "D4")
      (value "D_SMD")
      (footprint "eagle-import:D_SMD")
      (libsource (lib "eagle-import") (part "DIODOD_SMD"))
    )
    (comp (ref "D5")
      (value "D_SMD")
      (footprint "eagle-import:D_SMD")
      (libsource (lib "eagle-import") (part "DIODOD_SMD"))
    )
    (comp (ref "D6")
      (value "D_SMD")
      (footprint "eagle-import:D_SMD")
      (libsource (lib "eagle-import") (part "DIODOD_SMD"))
    )
    (comp (ref "D7")
      (value "D_SMD")
      (footprint "eagle-import:D_SMD")
      (libsource (lib "eagle-import") (part "DIODOD_SMD"))
    )
    (comp (ref "R55")
      (value "1k")
      (footprint "eagle-import:RESISTENCIA_0805")
      (libsource (lib "eagle-import") (part "RESISTORSMD_0805"))
    )
    (comp (ref "R56")
      (value "1k")
      (footprint "eagle-import:RESISTENCIA_0805")
      (libsource (lib "eagle-import") (part "RESISTORSMD_0805"))
    )
    (comp (ref "R57")
      (value "RSMD")
      (footprint "eagle-import:RESISTENCIA_0805")
      (libsource (lib "eagle-import") (part "RESISTORSMD_0805"))
    )
    (comp (ref "R58")
      (value "1k")
      (footprint "eagle-import:RESISTENCIA_0805")
      (libsource (lib "eagle-import") (part "RESISTORSMD_0805"))
    )
    (comp (ref "R59")
      (value "1k")
      (footprint "eagle-import:RESISTENCIA_0805")
      (libsource (lib "eagle-import") (part "RESISTORSMD_0805"))
    )
    (comp (ref "R60")
      (value "1k")
      (footprint "eagle-import:RESISTENCIA_0805")
      (libsource (lib "eagle-import") (part "RESISTORSMD_0805"))
    )
    (comp (ref "R61")
      (value "10k")
      (footprint "eagle-import:RESISTENCIA_0805")
      (libsource (lib "eagle-import") (part "RESISTORSMD_0805"))
    )
    (comp (ref "R62")
      (value "10k")
      (footprint "eagle-import:RESISTENCIA_0805")
      (libsource (lib "eagle-import") (part "RESISTORSMD_0805"))
    )
    (comp (ref "R63")
      (value "10k")
      (footprint "eagle-import:RESISTENCIA_0805")
      (libsource (lib "eagle-import") (part "RESISTORSMD_0805"))
    )
    (comp (ref "R64")
      (value "10k")
      (footprint "eagle-import:RESISTENCIA_0805")
      (libsource (lib "eagle-import") (part "RESISTORSMD_0805"))
    )
    (comp (ref "U6")
      (value "TL084")
      (footprint "eagle-import:SO14OP")
      (libsource (lib "eagle-import") (part "TL084_SMD"))
    )
    (comp (ref "U7")
      (value "TL082PS")
      (footprint "eagle-import:SOP08")
      (libsource (lib "eagle-import") (part "TL082PS"))
    )
    (comp (ref "VR9")
      (value "TRP")
      (footprint "eagle-import:TRIMPOT-PTH-3386U")
      (libsource (lib "eagle-import") (part "TRIMPOT_TH"))
    )
    (comp (ref "C18")
      (value "100nf")
      (footprint "eagle-import:CAP_CER_2,54-5X5")
      (libsource (lib "eagle-import") (part "CAP_CERAMICO_TH2"))
    )
    (comp (ref "C19")
      (value "100nf")
      (footprint "eagle-import:CAP_CER_2,54-5X5")
      (libsource (lib "eagle-import") (part "CAP_CERAMICO_TH2"))
    )
    (comp (ref "C20")
      (value "100nf")
      (footprint "eagle-import:CAP_CER_16X7")
      (libsource (lib "eagle-import") (part "CAP_CERAMICO_TH16"))
    )
    (comp (ref "C21")
      (value "100nf")
      (footprint "eagle-import:CAP_CER_16X7")
      (libsource (lib "eagle-import") (part "CAP_CERAMICO_TH16"))
    )
    (comp (ref "C26")
      (value "100nf")
      (footprint "eagle-import:CAP_CER_SMD-0805")
      (libsource (lib "eagle-import") (part "CAP_CERAMICO_SMD"))
    )
    (comp (ref "C27")
      (value "100nf")
      (footprint "eagle-import:CAP_CER_SMD-0805")
      (libsource (lib "eagle-import") (part "CAP_CERAMICO_SMD"))
    )
    (comp (ref "Q17")
      (value "TIP48_TH")
      (footprint "eagle-import:TO220")
      (libsource (lib "eagle-import") (part "TIP48_TH"))
    )
    (comp (ref "Q18")
      (value "TIP50_TH")
      (footprint "eagle-import:TO220")
      (libsource (lib "eagle-import") (part "TIP50_TH"))
    )
    (comp (ref "Q19")
      (value "TIP50_TH")
      (footprint "eagle-import:TO220")
      (libsource (lib "eagle-import") (part "TIP50_TH"))
    )
    (comp (ref "Q20")
      (value "TIP50_TH")
      (footprint "eagle-import:TO220")
      (libsource (lib "eagle-import") (part "TIP50_TH"))
    )
    (comp (ref "Q21")
      (value "TIP50_TH")
      (footprint "eagle-import:TO220")
      (libsource (lib "eagle-import") (part "TIP50_TH"))
    )
    (comp (ref "Q22")
      (value "TIP48_TH")
      (footprint "eagle-import:TO220")
      (libsource (lib "eagle-import") (part "TIP48_TH"))
    )
    (comp (ref "Q23")
      (value "TIP48_TH")
      (footprint "eagle-import:TO220")
      (libsource (lib "eagle-import") (part "TIP48_TH"))
    )
    (comp (ref "Q24")
      (value "TIP48_TH")
      (footprint "eagle-import:TO220")
      (libsource (lib "eagle-import") (part "TIP48_TH"))
    )
    (comp (ref "R31")
      (value "820R_SMD")
      (footprint "eagle-import:RESISTENCIA_0805")
      (libsource (lib "eagle-import") (part "RESISTORSMD_0805"))
    )
    (comp (ref "R32")
      (value "820R_SMD")
      (footprint "eagle-import:RESISTENCIA_0805")
      (libsource (lib "eagle-import") (part "RESISTORSMD_0805"))
    )
    (comp (ref "R33")
      (value "120R")
      (footprint "eagle-import:0204V")
      (libsource (lib "eagle-import") (part "RESISTORT_CORTO"))
    )
    (comp (ref "R34")
      (value "120R")
      (footprint "eagle-import:0204V")
      (libsource (lib "eagle-import") (part "RESISTORT_CORTO"))
    )
    (comp (ref "R35")
      (value "220R")
      (footprint "eagle-import:0204V")
      (libsource (lib "eagle-import") (part "RESISTORT_CORTO"))
    )
    (comp (ref "R36")
      (value "220R")
      (footprint "eagle-import:0204V")
      (libsource (lib "eagle-import") (part "RESISTORT_CORTO"))
    )
    (comp (ref "R37")
      (value "220R")
      (footprint "eagle-import:0204V")
      (libsource (lib "eagle-import") (part "RESISTORT_CORTO"))
    )
    (comp (ref "R38")
      (value "220R")
      (footprint "eagle-import:0204V")
      (libsource (lib "eagle-import") (part "RESISTORT_CORTO"))
    )
    (comp (ref "U4")
      (value "TL084")
      (footprint "eagle-import:SO14OP")
      (libsource (lib "eagle-import") (part "TL084_SMD"))
    )
    (comp (ref "VR5")
      (value "TRP")
      (footprint "eagle-import:TRIMPOT-PTH-3386U")
      (libsource (lib "eagle-import") (part "TRIMPOT_TH"))
    )
    (comp (ref "VR6")
      (value "TRP")
      (footprint "eagle-import:TRIMPOT-PTH-3386U")
      (libsource (lib "eagle-import") (part "TRIMPOT_TH"))
    )
  )
  (nets
    (net (code "1") (name "+5V") (class "Default")
      (node (ref "C1") (pin "1") (pinfunction "1_1") (pintype "passive"))
      (node (ref "C9") (pin "2") (pinfunction "2_2") (pintype "passive"))
      (node (ref "CON_AC") (pin "VIN") (pinfunction "VIN_VIN") (pintype "bidirectional"))
      (node (ref "CP2") (pin "+") (pinfunction "+_+") (pintype "passive"))
      (node (ref "IC1") (pin "14") (pinfunction "VCC_14") (pintype "power_in"))
      (node (ref "K1") (pin "1") (pinfunction "S_1") (pintype "passive"))
      (node (ref "REG1") (pin "OUT") (pinfunction "OUT_OUT") (pintype "passive"))
      (node (ref "U2") (pin "1") (pinfunction "VCC1_1") (pintype "power_in"))
      (node (ref "UC1") (pin "VIN") (pinfunction "VIN_VIN") (pintype "power_in"))
    )
    (net (code "2") (name "+5_ISO") (class "Default")
      (node (ref "C10") (pin "1") (pinfunction "1_1") (pintype "passive"))
      (node (ref "C11") (pin "1") (pinfunction "1_1") (pintype "passive"))
      (node (ref "CP5") (pin "+") (pinfunction "+_+") (pintype "passive"))
      (node (ref "D2") (pin "A") (pinfunction "A_A") (pintype "passive"))
      (node (ref "R13") (pin "2") (pinfunction "2_2") (pintype "passive"))
      (node (ref "REG3") (pin "OUT") (pinfunction "OUT_OUT") (pintype "passive"))
      (node (ref "U2") (pin "16") (pinfunction "VCC2_16") (pintype "power_in"))
    )
    (net (code "3") (name "+15HV") (class "Default")
      (node (ref "C16") (pin "2") (pinfunction "2_2") (pintype "passive"))
      (node (ref "C26") (pin "2") (pinfunction "2_2") (pintype "passive"))
      (node (ref "C28") (pin "2") (pinfunction "2_2") (pintype "passive"))
      (node (ref "C3") (pin "2") (pinfunction "2_2") (pintype "passive"))
      (node (ref "C30") (pin "2") (pinfunction "2_2") (pintype "passive"))
      (node (ref "C32") (pin "2") (pinfunction "2_2") (pintype "passive"))
      (node (ref "CP6") (pin "+") (pinfunction "+_+") (pintype "passive"))
      (node (ref "D3") (pin "A") (pinfunction "A_A") (pintype "passive"))
      (node (ref "K3") (pin "1") (pinfunction "S_1") (pintype "passive"))
      (node (ref "U1") (pin "4") (pinfunction "P$V+_4") (pintype "bidirectional"))
      (node (ref "U3") (pin "4") (pinfunction "P$V+_4") (pintype "bidirectional"))
      (node (ref "U4") (pin "4") (pinfunction "P$V+_4") (pintype "bidirectional"))
      (node (ref "U5") (pin "4") (pinfunction "P$V+_4") (pintype "bidirectional"))
      (node (ref "U6") (pin "4") (pinfunction "P$V+_4") (pintype "bidirectional"))
      (node (ref "U7") (pin "8") (pinfunction "V+_8") (pintype "power_in"))
    )
    (net (code "4") (name "+15V") (class "Default")
      (node (ref "D1") (pin "A") (pinfunction "A_A") (pintype "passive"))
      (node (ref "K2") (pin "1") (pinfunction "S_1") (pintype "passive"))
    )
    (net (code "5") (name "-15HV") (class "Default")
      (node (ref "C17") (pin "1") (pinfunction "1_1") (pintype "passive"))
      (node (ref "C27") (pin "1") (pinfunction "1_1") (pintype "passive"))
      (node (ref "C29") (pin "1") (pinfunction "1_1") (pintype "passive"))
      (node (ref "C31") (pin "1") (pinfunction "1_1") (pintype "passive"))
      (node (ref "C33") (pin "1") (pinfunction "1_1") (pintype "passive"))
      (node (ref "C4") (pin "1") (pinfunction "1_1") (pintype "passive"))
      (node (ref "CP7") (pin "+") (pinfunction "+_+") (pintype "passive"))
      (node (ref "K4") (pin "1") (pinfunction "S_1") (pintype "passive"))
      (node (ref "U1") (pin "11") (pinfunction "P$V-_11") (pintype "bidirectional"))
      (node (ref "U3") (pin "11") (pinfunction "P$V-_11") (pintype "bidirectional"))
      (node (ref "U4") (pin "11") (pinfunction "P$V-_11") (pintype "bidirectional"))
      (node (ref "U5") (pin "11") (pinfunction "P$V-_11") (pintype "bidirectional"))
      (node (ref "U6") (pin "11") (pinfunction "P$V-_11") (pintype "bidirectional"))
      (node (ref "U7") (pin "4") (pinfunction "V-_4") (pintype "power_in"))
    )
    (net (code "6") (name "3.3V") (class "Default")
      (node (ref "UC1") (pin "3.3V") (pinfunction "3.3V_3.3V") (pintype "power_in"))
    )
    (net (code "7") (name "CH1") (class "Default")
      (node (ref "DAC1") (pin "2") (pinfunction "VOUTA_2") (pintype "output"))
      (node (ref "U1") (pin "3") (pinfunction "+IN_3") (pintype "input"))
    )
    (net (code "8") (name "CH2") (class "Default")
      (node (ref "DAC1") (pin "3") (pinfunction "VOUTB_3") (pintype "output"))
      (node (ref "U3") (pin "3") (pinfunction "+IN_3") (pintype "input"))
    )
    (net (code "9") (name "CH3") (class "Default")
      (node (ref "DAC1") (pin "4") (pinfunction "VOUTC_4") (pintype "output"))
      (node (ref "U4") (pin "3") (pinfunction "+IN_3") (pintype "input"))
    )
    (net (code "10") (name "CH4") (class "Default")
      (node (ref "DAC1") (pin "5") (pinfunction "VOUTD_5") (pintype "output"))
      (node (ref "U5") (pin "3") (pinfunction "+IN_3") (pintype "input"))
    )
    (net (code "11") (name "C_CH1") (class "Default")
      (node (ref "IC1") (pin "1") (pinfunction "I_1") (pintype "input"))
      (node (ref "R16") (pin "1") (pinfunction "1_1") (pintype "passive"))
      (node (ref "R18") (pin "1") (pinfunction "1_1") (pintype "passive"))
    )
    (net (code "12") (name "C_CH1N") (class "Default")
      (node (ref "IC1") (pin "2") (pinfunction "O_2") (pintype "output"))
      (node (ref "R17") (pin "1") (pinfunction "1_1") (pintype "passive"))
    )
    (net (code "13") (name "C_CH2") (class "Default")
      (node (ref "IC1") (pin "3") (pinfunction "I_3") (pintype "input"))
      (node (ref "R15") (pin "1") (pinfunction "1_1") (pintype "passive"))
      (node (ref "R30") (pin "1") (pinfunction "1_1") (pintype "passive"))
    )
    (net (code "14") (name "C_CH2N") (class "Default")
      (node (ref "IC1") (pin "4") (pinfunction "O_4") (pintype "output"))
      (node (ref "R29") (pin "1") (pinfunction "1_1") (pintype "passive"))
    )
    (net (code "15") (name "C_CH3") (class "Default")
      (node (ref "IC1") (pin "5") (pinfunction "I_5") (pintype "input"))
      (node (ref "R14") (pin "1") (pinfunction "1_1") (pintype "passive"))
      (node (ref "R41") (pin "1") (pinfunction "1_1") (pintype "passive"))
    )
    (net (code "16") (name "C_CH3N") (class "Default")
      (node (ref "IC1") (pin "6") (pinfunction "O_6") (pintype "output"))
      (node (ref "R40") (pin "1") (pinfunction "1_1") (pintype "passive"))
    )
    (net (code "17") (name "C_CH4") (class "Default")
      (node (ref "IC1") (pin "9") (pinfunction "I_9") (pintype "input"))
      (node (ref "R12") (pin "1") (pinfunction "1_1") (pintype "passive"))
      (node (ref "R52") (pin "1") (pinfunction "1_1") (pintype "passive"))
    )
    (net (code "18") (name "C_CH4N") (class "Default")
      (node (ref "IC1") (pin "8") (pinfunction "O_8") (pintype "output"))
      (node (ref "R51") (pin "1") (pinfunction "1_1") (pintype "passive"))
    )
    (net (code "19") (name "DIN") (class "Default")
      (node (ref "U2") (pin "3") (pinfunction "INA_3") (pintype "passive"))
      (node (ref "UC1") (pin "11") (pinfunction "11/MOSI_11") (pintype "bidirectional"))
    )
    (net (code "20") (name "DIN_ISO") (class "Default")
      (node (ref "DAC1") (pin "8") (pinfunction "DIN_8") (pintype "input"))
      (node (ref "U2") (pin "14") (pinfunction "OUTA_14") (pintype "tri_state"))
    )
    (net (code "21") (name "GND") (class "Default")
      (node (ref "C1") (pin "2") (pinfunction "2_2") (pintype "passive"))
      (node (ref "C9") (pin "1") (pinfunction "1_1") (pintype "passive"))
      (node (ref "CON_AC") (pin "GND") (pinfunction "GND_GND") (pintype "bidirectional"))
      (node (ref "CP1") (pin "-") (pinfunction "-_-") (pintype "passive"))
      (node (ref "CP2") (pin "-") (pinfunction "-_-") (pintype "passive"))
      (node (ref "IC1") (pin "7") (pinfunction "GND_7") (pintype "power_in"))
      (node (ref "J1") (pin "1") (pinfunction "1_1") (pintype "passive"))
      (node (ref "J2") (pin "1") (pinfunction "1_1") (pintype "passive"))
      (node (ref "K1") (pin "2") (pinfunction "S_2") (pintype "passive"))
      (node (ref "K2") (pin "2") (pinfunction "S_2") (pintype "passive"))
      (node (ref "R1") (pin "1") (pinfunction "1_1") (pintype "passive"))
      (node (ref "R53") (pin "2") (pinfunction "2_2") (pintype "passive"))
      (node (ref "REG1") (pin "GND") (pinfunction "GND_GND") (pintype "input"))
      (node (ref "RL5") (pin "2") (pinfunction "C_2") (pintype "passive"))
      (node (ref "RL6") (pin "2") (pinfunction "C_2") (pintype "passive"))
      (node (ref "RL7") (pin "2") (pinfunction "C_2") (pintype "passive"))
      (node (ref "RL8") (pin "2") (pinfunction "C_2") (pintype "passive"))
      (node (ref "U2") (pin "2") (pinfunction "GND1_2") (pintype "power_in"))
      (node (ref "U2") (pin "8") (pinfunction "GND1_8") (pintype "power_in"))
      (node (ref "UC1") (pin "AGND") (pinfunction "AGND_AGND") (pintype "power_in"))
      (node (ref "UC1") (pin "GND") (pinfunction "GND_GND") (pintype "power_in"))
    )
    (net (code "22") (name "GPIO1") (class "Default")
      (node (ref "UC1") (pin "2") (pinfunction "2_2") (pintype "bidirectional"))
    )
    (net (code "23") (name "GPIO2") (class "Default")
      (node (ref "UC1") (pin "3") (pinfunction "3/PWM_3") (pintype "bidirectional"))
    )
    (net (code "24") (name "GPIO3") (class "Default")
      (node (ref "UC1") (pin "4") (pinfunction "4/PWM_4") (pintype "bidirectional"))
    )
    (net (code "25") (name "GPIO4") (class "Default")
      (node (ref "UC1") (pin "5") (pinfunction "5/PWM_5") (pintype "bidirectional"))
    )
    (net (code "26") (name "GS_CH1") (class "Default")
      (node (ref "U1") (pin "10") (pinfunction "+IN_10") (pintype "input"))
      (node (ref "U1") (pin "14") (pinfunction "OUT_14") (pintype "output"))
      (node (ref "U1") (pin "5") (pinfunction "+IN_5") (pintype "input"))
      (node (ref "U6") (pin "12") (pinfunction "+IN_12") (pintype "input"))
      (node (ref "U6") (pin "3") (pinfunction "+IN_3") (pintype "input"))
      (node (ref "VR2") (pin "2") (pinfunction "WIPER_2") (pintype "passive"))
      (node (ref "VR2") (pin "3") (pinfunction "CW_3") (pintype "passive"))
    )
    (net (code "27") (name "Net-(C5-Pad1)") (class "Default")
      (node (ref "C5") (pin "1") (pinfunction "1_1") (pintype "passive"))
      (node (ref "Q1") (pin "C") (pinfunction "C_C") (pintype "passive"))
      (node (ref "Q4") (pin "C") (pinfunction "C_C") (pintype "passive"))
      (node (ref "Q5") (pin "B") (pinfunction "B_B") (pintype "passive"))
    )
    (net (code "28") (name "Net-(C6-Pad2)") (class "Default")
      (node (ref "C6") (pin "2") (pinfunction "2_2") (pintype "passive"))
      (node (ref "Q2") (pin "C") (pinfunction "C_C") (pintype "passive"))
      (node (ref "Q6") (pin "C") (pinfunction "C_C") (pintype "passive"))
      (node (ref "Q7") (pin "B") (pinfunction "B_B") (pintype "passive"))
    )
    (net (code "29") (name "Net-(C12-Pad2)") (class "Default")
      (node (ref "C12") (pin "2") (pinfunction "2_2") (pintype "passive"))
      (node (ref "Q10") (pin "C") (pinfunction "C_C") (pintype "passive"))
      (node (ref "Q14") (pin "C") (pinfunction "C_C") (pintype "passive"))
      (node (ref "Q15") (pin "B") (pinfunction "B_B") (pintype "passive"))
    )
    (net (code "30") (name "Net-(C13-Pad1)") (class "Default")
      (node (ref "C13") (pin "1") (pinfunction "1_1") (pintype "passive"))
      (node (ref "Q12") (pin "C") (pinfunction "C_C") (pintype "passive"))
      (node (ref "Q13") (pin "B") (pinfunction "B_B") (pintype "passive"))
      (node (ref "Q9") (pin "C") (pinfunction "C_C") (pintype "passive"))
    )
    (net (code "31") (name "Net-(C18-Pad2)") (class "Default")
      (node (ref "C18") (pin "2") (pinfunction "2_2") (pintype "passive"))
      (node (ref "Q18") (pin "C") (pinfunction "C_C") (pintype "passive"))
      (node (ref "Q22") (pin "C") (pinfunction "C_C") (pintype "passive"))
      (node (ref "Q23") (pin "B") (pinfunction "B_B") (pintype "passive"))
    )
    (net (code "32") (name "Net-(C19-Pad1)") (class "Default")
      (node (ref "C19") (pin "1") (pinfunction "1_1") (pintype "passive"))
      (node (ref "Q17") (pin "C") (pinfunction "C_C") (pintype "passive"))
      (node (ref "Q20") (pin "C") (pinfunction "C_C") (pintype "passive"))
      (node (ref "Q21") (pin "B") (pinfunction "B_B") (pintype "passive"))
    )
    (net (code "33") (name "Net-(C22-Pad2)") (class "Default")
      (node (ref "C22") (pin "2") (pinfunction "2_2") (pintype "passive"))
      (node (ref "Q26") (pin "C") (pinfunction "C_C") (pintype "passive"))
      (node (ref "Q30") (pin "C") (pinfunction "C_C") (pintype "passive"))
      (node (ref "Q31") (pin "B") (pinfunction "B_B") (pintype "passive"))
    )
    (net (code "34") (name "Net-(C23-Pad1)") (class "Default")
      (node (ref "C23") (pin "1") (pinfunction "1_1") (pintype "passive"))
      (node (ref "Q25") (pin "C") (pinfunction "C_C") (pintype "passive"))
      (node (ref "Q28") (pin "C") (pinfunction "C_C") (pintype "passive"))
      (node (ref "Q29") (pin "B") (pinfunction "B_B") (pintype "passive"))
    )
    (net (code "35") (name "Net-(CP1-Pad+)") (class "Default")
      (node (ref "CP1") (pin "+") (pinfunction "+_+") (pintype "passive"))
      (node (ref "D1") (pin "C") (pinfunction "C_C") (pintype "passive"))
      (node (ref "LED1") (pin "A") (pinfunction "A_A") (pintype "passive"))
      (node (ref "REG1") (pin "IN") (pinfunction "IN_IN") (pintype "input"))
    )
    (net (code "36") (name "Net-(CP4-Pad+)") (class "Default")
      (node (ref "CP4") (pin "+") (pinfunction "+_+") (pintype "passive"))
      (node (ref "D3") (pin "C") (pinfunction "C_C") (pintype "passive"))
      (node (ref "LED3") (pin "A") (pinfunction "A_A") (pintype "passive"))
      (node (ref "REG3") (pin "IN") (pinfunction "IN_IN") (pintype "input"))
    )
    (net (code "37") (name "Net-(D4-C)") (class "Default")
      (node (ref "C35") (pin "2") (pinfunction "2_2") (pintype "passive"))
      (node (ref "D4") (pin "K") (pinfunction "C_K") (pintype "passive"))
      (node (ref "D5") (pin "A") (pinfunction "A_A") (pintype "passive"))
      (node (ref "U6") (pin "1") (pinfunction "OUT_1") (pintype "output"))
    )
    (net (code "38") (name "Net-(D5-C)") (class "Default")
      (node (ref "D5") (pin "K") (pinfunction "C_K") (pintype "passive"))
      (node (ref "R57") (pin "2") (pinfunction "2_2") (pintype "passive"))
      (node (ref "U6") (pin "5") (pinfunction "+IN_5") (pintype "input"))
    )
    (net (code "39") (name "Net-(D6-C)") (class "Default")
      (node (ref "C34") (pin "2") (pinfunction "2_2") (pintype "passive"))
      (node (ref "D6") (pin "K") (pinfunction "C_K") (pintype "passive"))
      (node (ref "D7") (pin "A") (pinfunction "A_A") (pintype "passive"))
      (node (ref "U6") (pin "14") (pinfunction "OUT_14") (pintype "output"))
    )
    (net (code "40") (name "Net-(D7-C)") (class "Default")
      (node (ref "D7") (pin "K") (pinfunction "C_K") (pintype "passive"))
      (node (ref "R60") (pin "2") (pinfunction "2_2") (pintype "passive"))
      (node (ref "U6") (pin "10") (pinfunction "+IN_10") (pintype "input"))
    )
    (net (code "41") (name "Net-(K1B-S)") (class "Default")
      (node (ref "K1") (pin "4") (pinfunction "S_4") (pintype "passive"))
      (node (ref "R53") (pin "1") (pinfunction "1_1") (pintype "passive"))
      (node (ref "R54") (pin "1") (pinfunction "1_1") (pintype "passive"))
    )
    (net (code "42") (name "Net-(K1C-S)") (class "Default")
      (node (ref "K1") (pin "3") (pinfunction "S_3") (pintype "passive"))
      (node (ref "UC1") (pin "0") (pinfunction "0/RX1/T_0") (pintype "bidirectional"))
    )
    (net (code "43") (name "Net-(K_CH1A-S)") (class "Default")
      (node (ref "K_CH1") (pin "1") (pinfunction "S_1") (pintype "passive"))
      (node (ref "RL2") (pin "4") (pinfunction "EMI_4") (pintype "passive"))
    )
    (net (code "44") (name "Net-(K_CH2A-S)") (class "Default")
      (node (ref "K_CH2") (pin "1") (pinfunction "S_1") (pintype "passive"))
      (node (ref "RL4") (pin "4") (pinfunction "EMI_4") (pintype "passive"))
    )
    (net (code "45") (name "Net-(K_CH3A-S)") (class "Default")
      (node (ref "K_CH3") (pin "1") (pinfunction "S_1") (pintype "passive"))
      (node (ref "RL6") (pin "4") (pinfunction "EMI_4") (pintype "passive"))
    )
    (net (code "46") (name "Net-(K_CH4A-S)") (class "Default")
      (node (ref "K_CH4") (pin "1") (pinfunction "S_1") (pintype "passive"))
      (node (ref "RL8") (pin "4") (pinfunction "EMI_4") (pintype "passive"))
    )
    (net (code "47") (name "Net-(LED1-PadC)") (class "Default")
      (node (ref "LED1") (pin "C") (pinfunction "C_C") (pintype "passive"))
      (node (ref "R1") (pin "2") (pinfunction "2_2") (pintype "passive"))
    )
    (net (code "48") (name "Net-(LED2-PadC)") (class "Default")
      (node (ref "LED2") (pin "C") (pinfunction "C_C") (pintype "passive"))
      (node (ref "R2") (pin "2") (pinfunction "2_2") (pintype "passive"))
    )
    (net (code "49") (name "Net-(LED3-PadC)") (class "Default")
      (node (ref "LED3") (pin "C") (pinfunction "C_C") (pintype "passive"))
      (node (ref "R11") (pin "2") (pinfunction "2_2") (pintype "passive"))
    )
    (net (code "50") (name "Net-(Q3-PadB)") (class "Default")
      (node (ref "Q3") (pin "B") (pinfunction "B_B") (pintype "passive"))
      (node (ref "Q3") (pin "C") (pinfunction "C_C") (pintype "passive"))
      (node (ref "Q4") (pin "B") (pinfunction "B_B") (pintype "passive"))
      (node (ref "Q5") (pin "E") (pinfunction "E_E") (pintype "passive"))
    )
    (net (code "51") (name "Net-(Q3-PadE)") (class "Default")
      (node (ref "Q3") (pin "E") (pinfunction "E_E") (pintype "passive"))
      (node (ref "R8") (pin "1") (pinfunction "1_1") (pintype "passive"))
    )
    (net (code "52") (name "Net-(Q4-PadE)") (class "Default")
      (node (ref "Q4") (pin "E") (pinfunction "E_E") (pintype "passive"))
      (node (ref "R7") (pin "1") (pinfunction "1_1") (pintype "passive"))
    )
    (net (code "53") (name "Net-(Q6-PadB)") (class "Default")
      (node (ref "Q6") (pin "B") (pinfunction "B_B") (pintype "passive"))
      (node (ref "Q7") (pin "E") (pinfunction "E_E") (pintype "passive"))
      (node (ref "Q8") (pin "B") (pinfunction "B_B") (pintype "passive"))
      (node (ref "Q8") (pin "C") (pinfunction "C_C") (pintype "passive"))
    )
    (net (code "54") (name "Net-(Q6-PadE)") (class "Default")
      (node (ref "Q6") (pin "E") (pinfunction "E_E") (pintype "passive"))
      (node (ref "R9") (pin "2") (pinfunction "2_2") (pintype "passive"))
    )
    (net (code "55") (name "Net-(Q8-PadE)") (class "Default")
      (node (ref "Q8") (pin "E") (pinfunction "E_E") (pintype "passive"))
      (node (ref "R10") (pin "2") (pinfunction "2_2") (pintype "passive"))
    )
    (net (code "56") (name "Net-(Q11-PadB)") (class "Default")
      (node (ref "Q11") (pin "B") (pinfunction "B_B") (pintype "passive"))
      (node (ref "Q11") (pin "C") (pinfunction "C_C") (pintype "passive"))
      (node (ref "Q12") (pin "B") (pinfunction "B_B") (pintype "passive"))
      (node (ref "Q13") (pin "E") (pinfunction "E_E") (pintype "passive"))
    )
    (net (code "57") (name "Net-(Q11-PadE)") (class "Default")
      (node (ref "Q11") (pin "E") (pinfunction "E_E") (pintype "passive"))
      (node (ref "R25") (pin "1") (pinfunction "1_1") (pintype "passive"))
    )
    (net (code "58") (name "Net-(Q12-PadE)") (class "Default")
      (node (ref "Q12") (pin "E") (pinfunction "E_E") (pintype "passive"))
      (node (ref "R24") (pin "1") (pinfunction "1_1") (pintype "passive"))
    )
    (net (code "59") (name "Net-(Q14-PadB)") (class "Default")
      (node (ref "Q14") (pin "B") (pinfunction "B_B") (pintype "passive"))
      (node (ref "Q15") (pin "E") (pinfunction "E_E") (pintype "passive"))
      (node (ref "Q16") (pin "B") (pinfunction "B_B") (pintype "passive"))
      (node (ref "Q16") (pin "C") (pinfunction "C_C") (pintype "passive"))
    )
    (net (code "60") (name "Net-(Q14-PadE)") (class "Default")
      (node (ref "Q14") (pin "E") (pinfunction "E_E") (pintype "passive"))
      (node (ref "R26") (pin "2") (pinfunction "2_2") (pintype "passive"))
    )
    (net (code "61") (name "Net-(Q16-PadE)") (class "Default")
      (node (ref "Q16") (pin "E") (pinfunction "E_E") (pintype "passive"))
      (node (ref "R27") (pin "2") (pinfunction "2_2") (pintype "passive"))
    )
    (net (code "62") (name "Net-(Q19-PadB)") (class "Default")
      (node (ref "Q19") (pin "B") (pinfunction "B_B") (pintype "passive"))
      (node (ref "Q19") (pin "C") (pinfunction "C_C") (pintype "passive"))
      (node (ref "Q20") (pin "B") (pinfunction "B_B") (pintype "passive"))
      (node (ref "Q21") (pin "E") (pinfunction "E_E") (pintype "passive"))
    )
    (net (code "63") (name "Net-(Q19-PadE)") (class "Default")
      (node (ref "Q19") (pin "E") (pinfunction "E_E") (pintype "passive"))
      (node (ref "R36") (pin "1") (pinfunction "1_1") (pintype "passive"))
    )
    (net (code "64") (name "Net-(Q20-PadE)") (class "Default")
      (node (ref "Q20") (pin "E") (pinfunction "E_E") (pintype "passive"))
      (node (ref "R35") (pin "1") (pinfunction "1_1") (pintype "passive"))
    )
    (net (code "65") (name "Net-(Q22-PadB)") (class "Default")
      (node (ref "Q22") (pin "B") (pinfunction "B_B") (pintype "passive"))
      (node (ref "Q23") (pin "E") (pinfunction "E_E") (pintype "passive"))
      (node (ref "Q24") (pin "B") (pinfunction "B_B") (pintype "passive"))
      (node (ref "Q24") (pin "C") (pinfunction "C_C") (pintype "passive"))
    )
    (net (code "66") (name "Net-(Q22-PadE)") (class "Default")
      (node (ref "Q22") (pin "E") (pinfunction "E_E") (pintype "passive"))
      (node (ref "R37") (pin "2") (pinfunction "2_2") (pintype "passive"))
    )
    (net (code "67") (name "Net-(Q24-PadE)") (class "Default")
      (node (ref "Q24") (pin "E") (pinfunction "E_E") (pintype "passive"))
      (node (ref "R38") (pin "2") (pinfunction "2_2") (pintype "passive"))
    )
    (net (code "68") (name "Net-(Q27-PadB)") (class "Default")
      (node (ref "Q27") (pin "B") (pinfunction "B_B") (pintype "passive"))
      (node (ref "Q27") (pin "C") (pinfunction "C_C") (pintype "passive"))
      (node (ref "Q28") (pin "B") (pinfunction "B_B") (pintype "passive"))
      (node (ref "Q29") (pin "E") (pinfunction "E_E") (pintype "passive"))
    )
    (net (code "69") (name "Net-(Q27-PadE)") (class "Default")
      (node (ref "Q27") (pin "E") (pinfunction "E_E") (pintype "passive"))
      (node (ref "R47") (pin "1") (pinfunction "1_1") (pintype "passive"))
    )
    (net (code "70") (name "Net-(Q28-PadE)") (class "Default")
      (node (ref "Q28") (pin "E") (pinfunction "E_E") (pintype "passive"))
      (node (ref "R46") (pin "1") (pinfunction "1_1") (pintype "passive"))
    )
    (net (code "71") (name "Net-(Q30-PadB)") (class "Default")
      (node (ref "Q30") (pin "B") (pinfunction "B_B") (pintype "passive"))
      (node (ref "Q31") (pin "E") (pinfunction "E_E") (pintype "passive"))
      (node (ref "Q32") (pin "B") (pinfunction "B_B") (pintype "passive"))
      (node (ref "Q32") (pin "C") (pinfunction "C_C") (pintype "passive"))
    )
    (net (code "72") (name "Net-(Q30-PadE)") (class "Default")
      (node (ref "Q30") (pin "E") (pinfunction "E_E") (pintype "passive"))
      (node (ref "R48") (pin "2") (pinfunction "2_2") (pintype "passive"))
    )
    (net (code "73") (name "Net-(Q32-PadE)") (class "Default")
      (node (ref "Q32") (pin "E") (pinfunction "E_E") (pintype "passive"))
      (node (ref "R49") (pin "2") (pinfunction "2_2") (pintype "passive"))
    )
    (net (code "74") (name "Net-(REG2-EN)") (class "Default")
      (node (ref "C2") (pin "1") (pinfunction "1_1") (pintype "passive"))
      (node (ref "D2") (pin "C") (pinfunction "C_C") (pintype "passive"))
      (node (ref "LED2") (pin "A") (pinfunction "A_A") (pintype "passive"))
      (node (ref "REG2") (pin "3") (pinfunction "EN_3") (pintype "input"))
      (node (ref "REG2") (pin "4") (pinfunction "VIN_4") (pintype "input"))
    )
    (net (code "75") (name "Net-(RL1-A)") (class "Default")
      (node (ref "R17") (pin "2") (pinfunction "2_2") (pintype "passive"))
      (node (ref "RL1") (pin "1") (pinfunction "A_1") (pintype "passive"))
    )
    (net (code "76") (name "Net-(RL1-C)") (class "Default")
      (node (ref "J1") (pin "2") (pinfunction "2_2") (pintype "passive"))
      (node (ref "RL1") (pin "2") (pinfunction "C_2") (pintype "passive"))
      (node (ref "RL2") (pin "2") (pinfunction "C_2") (pintype "passive"))
    )
    (net (code "77") (name "Net-(RL1-EMI)") (class "Default")
      (node (ref "R19") (pin "1") (pinfunction "1_1") (pintype "passive"))
      (node (ref "RL1") (pin "4") (pinfunction "EMI_4") (pintype "passive"))
    )
    (net (code "78") (name "Net-(RL2-A)") (class "Default")
      (node (ref "R18") (pin "2") (pinfunction "2_2") (pintype "passive"))
      (node (ref "RL2") (pin "1") (pinfunction "A_1") (pintype "passive"))
    )
    (net (code "79") (name "Net-(RL3-A)") (class "Default")
      (node (ref "R29") (pin "2") (pinfunction "2_2") (pintype "passive"))
      (node (ref "RL3") (pin "1") (pinfunction "A_1") (pintype "passive"))
    )
    (net (code "80") (name "Net-(RL3-C)") (class "Default")
      (node (ref "J2") (pin "2") (pinfunction "2_2") (pintype "passive"))
      (node (ref "RL3") (pin "2") (pinfunction "C_2") (pintype "passive"))
      (node (ref "RL4") (pin "2") (pinfunction "C_2") (pintype "passive"))
    )
    (net (code "81") (name "Net-(RL3-EMI)") (class "Default")
      (node (ref "R28") (pin "1") (pinfunction "1_1") (pintype "passive"))
      (node (ref "RL3") (pin "4") (pinfunction "EMI_4") (pintype "passive"))
    )
    (net (code "82") (name "Net-(RL4-A)") (class "Default")
      (node (ref "R30") (pin "2") (pinfunction "2_2") (pintype "passive"))
      (node (ref "RL4") (pin "1") (pinfunction "A_1") (pintype "passive"))
    )
    (net (code "83") (name "Net-(RL5-A)") (class "Default")
      (node (ref "R40") (pin "2") (pinfunction "2_2") (pintype "passive"))
      (node (ref "RL5") (pin "1") (pinfunction "A_1") (pintype "passive"))
    )
    (net (code "84") (name "Net-(RL5-EMI)") (class "Default")
      (node (ref "R39") (pin "1") (pinfunction "1_1") (pintype "passive"))
      (node (ref "RL5") (pin "4") (pinfunction "EMI_4") (pintype "passive"))
    )
    (net (code "85") (name "Net-(RL6-A)") (class "Default")
      (node (ref "R41") (pin "2") (pinfunction "2_2") (pintype "passive"))
      (node (ref "RL6") (pin "1") (pinfunction "A_1") (pintype "passive"))
    )
    (net (code "86") (name "Net-(RL7-A)") (class "Default")
      (node (ref "R51") (pin "2") (pinfunction "2_2") (pintype "passive"))
      (node (ref "RL7") (pin "1") (pinfunction "A_1") (pintype "passive"))
    )
    (net (code "87") (name "Net-(RL7-EMI)") (class "Default")
      (node (ref "R50") (pin "1") (pinfunction "1_1") (pintype "passive"))
      (node (ref "RL7") (pin "4") (pinfunction "EMI_4") (pintype "passive"))
    )
    (net (code "88") (name "Net-(RL8-A)") (class "Default")
      (node (ref "R52") (pin "2") (pinfunction "2_2") (pintype "passive"))
      (node (ref "RL8") (pin "1") (pinfunction "A_1") (pintype "passive"))
    )
    (net (code "89") (name "Net-(U1A--IN)") (class "Default")
      (node (ref "R3") (pin "2") (pinfunction "2_2") (pintype "passive"))
      (node (ref "U1") (pin "2") (pinfunction "-IN_2") (pintype "input"))
      (node (ref "VR1") (pin "3") (pinfunction "CW_3") (pintype "passive"))
    )
    (net (code "90") (name "Net-(U1A-OUT)") (class "Default")
      (node (ref "U1") (pin "1") (pinfunction "OUT_1") (pintype "output"))
      (node (ref "U1") (pin "12") (pinfunction "+IN_12") (pintype "input"))
      (node (ref "VR1") (pin "1") (pinfunction "CCW_1") (pintype "passive"))
      (node (ref "VR1") (pin "2") (pinfunction "WIPER_2") (pintype "passive"))
    )
    (net (code "91") (name "Net-(U1B--IN)") (class "Default")
      (node (ref "Q2") (pin "E") (pinfunction "E_E") (pintype "passive"))
      (node (ref "R6") (pin "2") (pinfunction "2_2") (pintype "passive"))
      (node (ref "U1") (pin "6") (pinfunction "-IN_6") (pintype "input"))
    )
    (net (code "92") (name "Net-(U1B-OUT)") (class "Default")
      (node (ref "Q2") (pin "B") (pinfunction "B_B") (pintype "passive"))
      (node (ref "U1") (pin "7") (pinfunction "OUT_7") (pintype "output"))
    )
    (net (code "93") (name "Net-(U1C--IN)") (class "Default")
      (node (ref "Q1") (pin "E") (pinfunction "E_E") (pintype "passive"))
      (node (ref "R5") (pin "2") (pinfunction "2_2") (pintype "passive"))
      (node (ref "U1") (pin "9") (pinfunction "-IN_9") (pintype "input"))
    )
    (net (code "94") (name "Net-(U1C-OUT)") (class "Default")
      (node (ref "Q1") (pin "B") (pinfunction "B_B") (pintype "passive"))
      (node (ref "U1") (pin "8") (pinfunction "OUT_8") (pintype "output"))
    )
    (net (code "95") (name "Net-(U1D--IN)") (class "Default")
      (node (ref "R4") (pin "2") (pinfunction "2_2") (pintype "passive"))
      (node (ref "U1") (pin "13") (pinfunction "-IN_13") (pintype "input"))
      (node (ref "VR2") (pin "1") (pinfunction "CCW_1") (pintype "passive"))
    )
    (net (code "96") (name "Net-(U2-EN)") (class "Default")
      (node (ref "R13") (pin "1") (pinfunction "1_1") (pintype "passive"))
      (node (ref "U2") (pin "10") (pinfunction "EN_10") (pintype "passive"))
    )
    (net (code "97") (name "Net-(U3A--IN)") (class "Default")
      (node (ref "R20") (pin "2") (pinfunction "2_2") (pintype "passive"))
      (node (ref "U3") (pin "2") (pinfunction "-IN_2") (pintype "input"))
      (node (ref "VR3") (pin "3") (pinfunction "CW_3") (pintype "passive"))
    )
    (net (code "98") (name "Net-(U3A-OUT)") (class "Default")
      (node (ref "U3") (pin "1") (pinfunction "OUT_1") (pintype "output"))
      (node (ref "U3") (pin "12") (pinfunction "+IN_12") (pintype "input"))
      (node (ref "VR3") (pin "1") (pinfunction "CCW_1") (pintype "passive"))
      (node (ref "VR3") (pin "2") (pinfunction "WIPER_2") (pintype "passive"))
    )
    (net (code "99") (name "Net-(U3B-+IN)") (class "Default")
      (node (ref "U3") (pin "10") (pinfunction "+IN_10") (pintype "input"))
      (node (ref "U3") (pin "14") (pinfunction "OUT_14") (pintype "output"))
      (node (ref "U3") (pin "5") (pinfunction "+IN_5") (pintype "input"))
      (node (ref "VR4") (pin "2") (pinfunction "WIPER_2") (pintype "passive"))
      (node (ref "VR4") (pin "3") (pinfunction "CW_3") (pintype "passive"))
    )
    (net (code "100") (name "Net-(U3B--IN)") (class "Default")
      (node (ref "Q10") (pin "E") (pinfunction "E_E") (pintype "passive"))
      (node (ref "R23") (pin "2") (pinfunction "2_2") (pintype "passive"))
      (node (ref "U3") (pin "6") (pinfunction "-IN_6") (pintype "input"))
    )
    (net (code "101") (name "Net-(U3B-OUT)") (class "Default")
      (node (ref "Q10") (pin "B") (pinfunction "B_B") (pintype "passive"))
      (node (ref "U3") (pin "7") (pinfunction "OUT_7") (pintype "output"))
    )
    (net (code "102") (name "Net-(U3C--IN)") (class "Default")
      (node (ref "Q9") (pin "E") (pinfunction "E_E") (pintype "passive"))
      (node (ref "R22") (pin "2") (pinfunction "2_2") (pintype "passive"))
      (node (ref "U3") (pin "9") (pinfunction "-IN_9") (pintype "input"))
    )
    (net (code "103") (name "Net-(U3C-OUT)") (class "Default")
      (node (ref "Q9") (pin "B") (pinfunction "B_B") (pintype "passive"))
      (node (ref "U3") (pin "8") (pinfunction "OUT_8") (pintype "output"))
    )
    (net (code "104") (name "Net-(U3D--IN)") (class "Default")
      (node (ref "R21") (pin "2") (pinfunction "2_2") (pintype "passive"))
      (node (ref "U3") (pin "13") (pinfunction "-IN_13") (pintype "input"))
      (node (ref "VR4") (pin "1") (pinfunction "CCW_1") (pintype "passive"))
    )
    (net (code "105") (name "Net-(U4A--IN)") (class "Default")
      (node (ref "R31") (pin "2") (pinfunction "2_2") (pintype "passive"))
      (node (ref "U4") (pin "2") (pinfunction "-IN_2") (pintype "input"))
      (node (ref "VR5") (pin "3") (pinfunction "CW_3") (pintype "passive"))
    )
    (net (code "106") (name "Net-(U4A-OUT)") (class "Default")
      (node (ref "U4") (pin "1") (pinfunction "OUT_1") (pintype "output"))
      (node (ref "U4") (pin "12") (pinfunction "+IN_12") (pintype "input"))
      (node (ref "VR5") (pin "1") (pinfunction "CCW_1") (pintype "passive"))
      (node (ref "VR5") (pin "2") (pinfunction "WIPER_2") (pintype "passive"))
    )
    (net (code "107") (name "Net-(U4B-+IN)") (class "Default")
      (node (ref "U4") (pin "10") (pinfunction "+IN_10") (pintype "input"))
      (node (ref "U4") (pin "14") (pinfunction "OUT_14") (pintype "output"))
      (node (ref "U4") (pin "5") (pinfunction "+IN_5") (pintype "input"))
      (node (ref "VR6") (pin "2") (pinfunction "WIPER_2") (pintype "passive"))
      (node (ref "VR6") (pin "3") (pinfunction "CW_3") (pintype "passive"))
    )
    (net (code "108") (name "Net-(U4B--IN)") (class "Default")
      (node (ref "Q18") (pin "E") (pinfunction "E_E") (pintype "passive"))
      (node (ref "R34") (pin "2") (pinfunction "2_2") (pintype "passive"))
      (node (ref "U4") (pin "6") (pinfunction "-IN_6") (pintype "input"))
    )
    (net (code "109") (name "Net-(U4B-OUT)") (class "Default")
      (node (ref "Q18") (pin "B") (pinfunction "B_B") (pintype "passive"))
      (node (ref "U4") (pin "7") (pinfunction "OUT_7") (pintype "output"))
    )
    (net (code "110") (name "Net-(U4C--IN)") (class "Default")
      (node (ref "Q17") (pin "E") (pinfunction "E_E") (pintype "passive"))
      (node (ref "R33") (pin "2") (pinfunction "2_2") (pintype "passive"))
      (node (ref "U4") (pin "9") (pinfunction "-IN_9") (pintype "input"))
    )
    (net (code "111") (name "Net-(U4C-OUT)") (class "Default")
      (node (ref "Q17") (pin "B") (pinfunction "B_B") (pintype "passive"))
      (node (ref "U4") (pin "8") (pinfunction "OUT_8") (pintype "output"))
    )
    (net (code "112") (name "Net-(U4D--IN)") (class "Default")
      (node (ref "R32") (pin "2") (pinfunction "2_2") (pintype "passive"))
      (node (ref "U4") (pin "13") (pinfunction "-IN_13") (pintype "input"))
      (node (ref "VR6") (pin "1") (pinfunction "CCW_1") (pintype "passive"))
    )
    (net (code "113") (name "Net-(U5A--IN)") (class "Default")
      (node (ref "R42") (pin "2") (pinfunction "2_2") (pintype "passive"))
      (node (ref "U5") (pin "2") (pinfunction "-IN_2") (pintype "input"))
      (node (ref "VR7") (pin "3") (pinfunction "CW_3") (pintype "passive"))
    )
    (net (code "114") (name "Net-(U5A-OUT)") (class "Default")
      (node (ref "U5") (pin "1") (pinfunction "OUT_1") (pintype "output"))
      (node (ref "U5") (pin "12") (pinfunction "+IN_12") (pintype "input"))
      (node (ref "VR7") (pin "1") (pinfunction "CCW_1") (pintype "passive"))
      (node (ref "VR7") (pin "2") (pinfunction "WIPER_2") (pintype "passive"))
    )
    (net (code "115") (name "Net-(U5B-+IN)") (class "Default")
      (node (ref "U5") (pin "10") (pinfunction "+IN_10") (pintype "input"))
      (node (ref "U5") (pin "14") (pinfunction "OUT_14") (pintype "output"))
      (node (ref "U5") (pin "5") (pinfunction "+IN_5") (pintype "input"))
      (node (ref "VR8") (pin "2") (pinfunction "WIPER_2") (pintype "passive"))
      (node (ref "VR8") (pin "3") (pinfunction "CW_3") (pintype "passive"))
    )
    (net (code "116") (name "Net-(U5B--IN)") (class "Default")
      (node (ref "Q26") (pin "E") (pinfunction "E_E") (pintype "passive"))
      (node (ref "R45") (pin "2") (pinfunction "2_2") (pintype "passive"))
      (node (ref "U5") (pin "6") (pinfunction "-IN_6") (pintype "input"))
    )
    (net (code "117") (name "Net-(U5B-OUT)") (class "Default")
      (node (ref "Q26") (pin "B") (pinfunction "B_B") (pintype "passive"))
      (node (ref "U5") (pin "7") (pinfunction "OUT_7") (pintype "output"))
    )
    (net (code "118") (name "Net-(U5C--IN)") (class "Default")
      (node (ref "Q25") (pin "E") (pinfunction "E_E") (pintype "passive"))
      (node (ref "R44") (pin "2") (pinfunction "2_2") (pintype "passive"))
      (node (ref "U5") (pin "9") (pinfunction "-IN_9") (pintype "input"))
    )
    (net (code "119") (name "Net-(U5C-OUT)") (class "Default")
      (node (ref "Q25") (pin "B") (pinfunction "B_B") (pintype "passive"))
      (node (ref "U5") (pin "8") (pinfunction "OUT_8") (pintype "output"))
    )
    (net (code "120") (name "Net-(U5D--IN)") (class "Default")
      (node (ref "R43") (pin "2") (pinfunction "2_2") (pintype "passive"))
      (node (ref "U5") (pin "13") (pinfunction "-IN_13") (pintype "input"))
      (node (ref "VR8") (pin "1") (pinfunction "CCW_1") (pintype "passive"))
    )
    (net (code "121") (name "Net-(U6A--IN)") (class "Default")
      (node (ref "C35") (pin "1") (pinfunction "1_1") (pintype "passive"))
      (node (ref "D4") (pin "A") (pinfunction "A_A") (pintype "passive"))
      (node (ref "R55") (pin "1") (pinfunction "1_1") (pintype "passive"))
      (node (ref "U6") (pin "2") (pinfunction "-IN_2") (pintype "input"))
    )
    (net (code "122") (name "Net-(U6B--IN)") (class "Default")
      (node (ref "R55") (pin "2") (pinfunction "2_2") (pintype "passive"))
      (node (ref "R56") (pin "1") (pinfunction "1_1") (pintype "passive"))
      (node (ref "U6") (pin "6") (pinfunction "-IN_6") (pintype "input"))
    )
    (net (code "123") (name "Net-(U6B-OUT)") (class "Default")
      (node (ref "R56") (pin "2") (pinfunction "2_2") (pintype "passive"))
      (node (ref "R61") (pin "1") (pinfunction "1_1") (pintype "passive"))
      (node (ref "U6") (pin "7") (pinfunction "OUT_7") (pintype "output"))
    )
    (net (code "124") (name "Net-(U6C--IN)") (class "Default")
      (node (ref "R58") (pin "2") (pinfunction "2_2") (pintype "passive"))
      (node (ref "R59") (pin "1") (pinfunction "1_1") (pintype "passive"))
      (node (ref "U6") (pin "9") (pinfunction "-IN_9") (pintype "input"))
    )
    (net (code "125") (name "Net-(U6C-OUT)") (class "Default")
      (node (ref "R59") (pin "2") (pinfunction "2_2") (pintype "passive"))
      (node (ref "R63") (pin "1") (pinfunction "1_1") (pintype "passive"))
      (node (ref "U6") (pin "8") (pinfunction "OUT_8") (pintype "output"))
    )
    (net (code "126") (name "Net-(U6D--IN)") (class "Default")
      (node (ref "C34") (pin "1") (pinfunction "1_1") (pintype "passive"))
      (node (ref "D6") (pin "A") (pinfunction "A_A") (pintype "passive"))
      (node (ref "R58") (pin "1") (pinfunction "1_1") (pintype "passive"))
      (node (ref "U6") (pin "13") (pinfunction "-IN_13") (pintype "input"))
    )
    (net (code "127") (name "Net-(U7A-+IN)") (class "Default")
      (node (ref "U7") (pin "1") (pinfunction "OUT_1") (pintype "output"))
      (node (ref "U7") (pin "3") (pinfunction "+IN_3") (pintype "input"))
      (node (ref "VR9") (pin "3") (pinfunction "CW_3") (pintype "passive"))
    )
    (net (code "128") (name "Net-(U7B-+IN)") (class "Default")
      (node (ref "R61") (pin "2") (pinfunction "2_2") (pintype "passive"))
      (node (ref "R62") (pin "1") (pinfunction "1_1") (pintype "passive"))
      (node (ref "U7") (pin "5") (pinfunction "+IN_5") (pintype "input"))
    )
    (net (code "129") (name "Net-(U7B--IN)") (class "Default")
      (node (ref "R63") (pin "2") (pinfunction "2_2") (pintype "passive"))
      (node (ref "R64") (pin "2") (pinfunction "2_2") (pintype "passive"))
      (node (ref "U7") (pin "6") (pinfunction "-IN_6") (pintype "input"))
    )
    (net (code "130") (name "Net-(U7B-OUT)") (class "Default")
      (node (ref "R62") (pin "2") (pinfunction "2_2") (pintype "passive"))
      (node (ref "U7") (pin "7") (pinfunction "OUT_7") (pintype "output"))
    )
    (net (code "131") (name "Net-(UC1-1{slash}TX1{slash}T)") (class "Default")
      (node (ref "R54") (pin "2") (pinfunction "2_2") (pintype "passive"))
      (node (ref "UC1") (pin "1") (pinfunction "1/TX1/T_1") (pintype "bidirectional"))
    )
    (net (code "132") (name "Net-(UC1-6{slash}PWM)") (class "Default")
      (node (ref "R16") (pin "2") (pinfunction "2_2") (pintype "passive"))
      (node (ref "UC1") (pin "6") (pinfunction "6/PWM_6") (pintype "bidirectional"))
    )
    (net (code "133") (name "Net-(UC1-7{slash}RX3)") (class "Default")
      (node (ref "R15") (pin "2") (pinfunction "2_2") (pintype "passive"))
      (node (ref "UC1") (pin "7") (pinfunction "7/RX3_7") (pintype "bidirectional"))
    )
    (net (code "134") (name "Net-(UC1-8{slash}TX3)") (class "Default")
      (node (ref "R14") (pin "2") (pinfunction "2_2") (pintype "passive"))
      (node (ref "UC1") (pin "8") (pinfunction "8/TX3_8") (pintype "bidirectional"))
    )
    (net (code "135") (name "Net-(UC1-9{slash}RX2{slash}PWM)") (class "Default")
      (node (ref "R12") (pin "2") (pinfunction "2_2") (pintype "passive"))
      (node (ref "UC1") (pin "9") (pinfunction "9/RX2/PWM_9") (pintype "bidirectional"))
    )
    (net (code "136") (name "PE") (class "Default")
      (node (ref "C10") (pin "2") (pinfunction "2_2") (pintype "passive"))
      (node (ref "C11") (pin "2") (pinfunction "2_2") (pintype "passive"))
      (node (ref "C12") (pin "1") (pinfunction "1_1") (pintype "passive"))
      (node (ref "C13") (pin "2") (pinfunction "2_2") (pintype "passive"))
      (node (ref "C14") (pin "1") (pinfunction "1_1") (pintype "passive"))
      (node (ref "C15") (pin "1") (pinfunction "1_1") (pintype "passive"))
      (node (ref "C16") (pin "1") (pinfunction "1_1") (pintype "passive"))
      (node (ref "C17") (pin "2") (pinfunction "2_2") (pintype "passive"))
      (node (ref "C18") (pin "1") (pinfunction "1_1") (pintype "passive"))
      (node (ref "C19") (pin "2") (pinfunction "2_2") (pintype "passive"))
      (node (ref "C2") (pin "2") (pinfunction "2_2") (pintype "passive"))
      (node (ref "C20") (pin "1") (pinfunction "1_1") (pintype "passive"))
      (node (ref "C21") (pin "1") (pinfunction "1_1") (pintype "passive"))
      (node (ref "C22") (pin "1") (pinfunction "1_1") (pintype "passive"))
      (node (ref "C23") (pin "2") (pinfunction "2_2") (pintype "passive"))
      (node (ref "C24") (pin "1") (pinfunction "1_1") (pintype "passive"))
      (node (ref "C25") (pin "1") (pinfunction "1_1") (pintype "passive"))
      (node (ref "C26") (pin "1") (pinfunction "1_1") (pintype "passive"))
      (node (ref "C27") (pin "2") (pinfunction "2_2") (pintype "passive"))
      (node (ref "C28") (pin "1") (pinfunction "1_1") (pintype "passive"))
      (node (ref "C29") (pin "2") (pinfunction "2_2") (pintype "passive"))
      (node (ref "C3") (pin "1") (pinfunction "1_1") (pintype "passive"))
      (node (ref "C30") (pin "1") (pinfunction "1_1") (pintype "passive"))
      (node (ref "C31") (pin "2") (pinfunction "2_2") (pintype "passive"))
      (node (ref "C32") (pin "1") (pinfunction "1_1") (pintype "passive"))
      (node (ref "C33") (pin "2") (pinfunction "2_2") (pintype "passive"))
      (node (ref "C4") (pin "2") (pinfunction "2_2") (pintype "passive"))
      (node (ref "C5") (pin "2") (pinfunction "2_2") (pintype "passive"))
      (node (ref "C6") (pin "1") (pinfunction "1_1") (pintype "passive"))
      (node (ref "C7") (pin "1") (pinfunction "1_1") (pintype "passive"))
      (node (ref "C8") (pin "1") (pinfunction "1_1") (pintype "passive"))
      (node (ref "CP3") (pin "-") (pinfunction "-_-") (pintype "passive"))
      (node (ref "CP4") (pin "-") (pinfunction "-_-") (pintype "passive"))
      (node (ref "CP5") (pin "-") (pinfunction "-_-") (pintype "passive"))
      (node (ref "CP6") (pin "-") (pinfunction "-_-") (pintype "passive"))
      (node (ref "CP7") (pin "-") (pinfunction "-_-") (pintype "passive"))
      (node (ref "DAC1") (pin "6") (pinfunction "GND_6") (pintype "power_in"))
      (node (ref "K3") (pin "2") (pinfunction "S_2") (pintype "passive"))
      (node (ref "K4") (pin "2") (pinfunction "S_2") (pintype "passive"))
      (node (ref "K5") (pin "2") (pinfunction "S_2") (pintype "passive"))
      (node (ref "K6") (pin "2") (pinfunction "S_2") (pintype "passive"))
      (node (ref "K_CH1") (pin "2") (pinfunction "S_2") (pintype "passive"))
      (node (ref "K_CH2") (pin "2") (pinfunction "S_2") (pintype "passive"))
      (node (ref "K_CH3") (pin "2") (pinfunction "S_2") (pintype "passive"))
      (node (ref "K_CH4") (pin "2") (pinfunction "S_2") (pintype "passive"))
      (node (ref "R11") (pin "1") (pinfunction "1_1") (pintype "passive"))
      (node (ref "R19") (pin "2") (pinfunction "2_2") (pintype "passive"))
      (node (ref "R2") (pin "1") (pinfunction "1_1") (pintype "passive"))
      (node (ref "R21") (pin "1") (pinfunction "1_1") (pintype "passive"))
      (node (ref "R22") (pin "1") (pinfunction "1_1") (pintype "passive"))
      (node (ref "R23") (pin "1") (pinfunction "1_1") (pintype "passive"))
      (node (ref "R28") (pin "2") (pinfunction "2_2") (pintype "passive"))
      (node (ref "R32") (pin "1") (pinfunction "1_1") (pintype "passive"))
      (node (ref "R33") (pin "1") (pinfunction "1_1") (pintype "passive"))
      (node (ref "R34") (pin "1") (pinfunction "1_1") (pintype "passive"))
      (node (ref "R39") (pin "2") (pinfunction "2_2") (pintype "passive"))
      (node (ref "R4") (pin "1") (pinfunction "1_1") (pintype "passive"))
      (node (ref "R43") (pin "1") (pinfunction "1_1") (pintype "passive"))
      (node (ref "R44") (pin "1") (pinfunction "1_1") (pintype "passive"))
      (node (ref "R45") (pin "1") (pinfunction "1_1") (pintype "passive"))
      (node (ref "R5") (pin "1") (pinfunction "1_1") (pintype "passive"))
      (node (ref "R50") (pin "2") (pinfunction "2_2") (pintype "passive"))
      (node (ref "R57") (pin "1") (pinfunction "1_1") (pintype "passive"))
      (node (ref "R6") (pin "1") (pinfunction "1_1") (pintype "passive"))
      (node (ref "R60") (pin "1") (pinfunction "1_1") (pintype "passive"))
      (node (ref "R64") (pin "1") (pinfunction "1_1") (pintype "passive"))
      (node (ref "REG2") (pin "2") (pinfunction "GND_2") (pintype "bidirectional"))
      (node (ref "REG3") (pin "GND") (pinfunction "GND_GND") (pintype "input"))
      (node (ref "U2") (pin "15") (pinfunction "GND2_15") (pintype "power_in"))
      (node (ref "U2") (pin "9") (pinfunction "GND2_9") (pintype "power_in"))
      (node (ref "VR9") (pin "1") (pinfunction "CCW_1") (pintype "passive"))
    )
    (net (code "137") (name "SCL") (class "Default")
      (node (ref "CON_AC") (pin "SCL") (pinfunction "SCL_SCL") (pintype "bidirectional"))
      (node (ref "UC1") (pin "19/A5") (pinfunction "19/A5/T/SCL_19/A5") (pintype "bidirectional"))
    )
    (net (code "138") (name "SCLK") (class "Default")
      (node (ref "U2") (pin "5") (pinfunction "INC_5") (pintype "passive"))
      (node (ref "UC1") (pin "13") (pinfunction "13/SCK/LED_13") (pintype "bidirectional"))
    )
    (net (code "139") (name "SCLK_ISO") (class "Default")
      (node (ref "DAC1") (pin "10") (pinfunction "SCLK_10") (pintype "input"))
      (node (ref "U2") (pin "12") (pinfunction "OUTC_12") (pintype "tri_state"))
    )
    (net (code "140") (name "SDA") (class "Default")
      (node (ref "CON_AC") (pin "SDA") (pinfunction "SDA_SDA") (pintype "bidirectional"))
      (node (ref "UC1") (pin "18/A4") (pinfunction "18/A4/T/SDA_18/A4") (pintype "bidirectional"))
    )
    (net (code "141") (name "S_CH1") (class "Default")
      (node (ref "Q5") (pin "C") (pinfunction "C_C") (pintype "passive"))
      (node (ref "Q7") (pin "C") (pinfunction "C_C") (pintype "passive"))
      (node (ref "RL1") (pin "6") (pinfunction "BAS_6") (pintype "passive"))
      (node (ref "RL2") (pin "6") (pinfunction "BAS_6") (pintype "passive"))
    )
    (net (code "142") (name "S_CH2") (class "Default")
      (node (ref "Q13") (pin "C") (pinfunction "C_C") (pintype "passive"))
      (node (ref "Q15") (pin "C") (pinfunction "C_C") (pintype "passive"))
      (node (ref "RL3") (pin "6") (pinfunction "BAS_6") (pintype "passive"))
      (node (ref "RL4") (pin "6") (pinfunction "BAS_6") (pintype "passive"))
    )
    (net (code "143") (name "S_CH3") (class "Default")
      (node (ref "Q21") (pin "C") (pinfunction "C_C") (pintype "passive"))
      (node (ref "Q23") (pin "C") (pinfunction "C_C") (pintype "passive"))
      (node (ref "RL5") (pin "6") (pinfunction "BAS_6") (pintype "passive"))
      (node (ref "RL6") (pin "6") (pinfunction "BAS_6") (pintype "passive"))
    )
    (net (code "144") (name "S_CH4") (class "Default")
      (node (ref "Q29") (pin "C") (pinfunction "C_C") (pintype "passive"))
      (node (ref "Q31") (pin "C") (pinfunction "C_C") (pintype "passive"))
      (node (ref "RL7") (pin "6") (pinfunction "BAS_6") (pintype "passive"))
      (node (ref "RL8") (pin "6") (pinfunction "BAS_6") (pintype "passive"))
    )
    (net (code "145") (name "V+") (class "Default")
      (node (ref "C15") (pin "2") (pinfunction "2_2") (pintype "passive"))
      (node (ref "C21") (pin "2") (pinfunction "2_2") (pintype "passive"))
      (node (ref "C25") (pin "2") (pinfunction "2_2") (pintype "passive"))
      (node (ref "C8") (pin "2") (pinfunction "2_2") (pintype "passive"))
      (node (ref "K5") (pin "1") (pinfunction "S_1") (pintype "passive"))
      (node (ref "R24") (pin "2") (pinfunction "2_2") (pintype "passive"))
      (node (ref "R25") (pin "2") (pinfunction "2_2") (pintype "passive"))
      (node (ref "R35") (pin "2") (pinfunction "2_2") (pintype "passive"))
      (node (ref "R36") (pin "2") (pinfunction "2_2") (pintype "passive"))
      (node (ref "R46") (pin "2") (pinfunction "2_2") (pintype "passive"))
      (node (ref "R47") (pin "2") (pinfunction "2_2") (pintype "passive"))
      (node (ref "R7") (pin "2") (pinfunction "2_2") (pintype "passive"))
      (node (ref "R8") (pin "2") (pinfunction "2_2") (pintype "passive"))
    )
    (net (code "146") (name "V-") (class "Default")
      (node (ref "C14") (pin "2") (pinfunction "2_2") (pintype "passive"))
      (node (ref "C20") (pin "2") (pinfunction "2_2") (pintype "passive"))
      (node (ref "C24") (pin "2") (pinfunction "2_2") (pintype "passive"))
      (node (ref "C7") (pin "2") (pinfunction "2_2") (pintype "passive"))
      (node (ref "K6") (pin "1") (pinfunction "S_1") (pintype "passive"))
      (node (ref "R10") (pin "1") (pinfunction "1_1") (pintype "passive"))
      (node (ref "R26") (pin "1") (pinfunction "1_1") (pintype "passive"))
      (node (ref "R27") (pin "1") (pinfunction "1_1") (pintype "passive"))
      (node (ref "R37") (pin "1") (pinfunction "1_1") (pintype "passive"))
      (node (ref "R38") (pin "1") (pinfunction "1_1") (pintype "passive"))
      (node (ref "R48") (pin "1") (pinfunction "1_1") (pintype "passive"))
      (node (ref "R49") (pin "1") (pinfunction "1_1") (pintype "passive"))
      (node (ref "R9") (pin "1") (pinfunction "1_1") (pintype "passive"))
    )
    (net (code "147") (name "VREF") (class "Default")
      (node (ref "CP3") (pin "+") (pinfunction "+_+") (pintype "passive"))
      (node (ref "DAC1") (pin "1") (pinfunction "VA_1") (pintype "power_in"))
      (node (ref "DAC1") (pin "7") (pinfunction "VREFIN_7") (pintype "input"))
      (node (ref "R20") (pin "1") (pinfunction "1_1") (pintype "passive"))
      (node (ref "R3") (pin "1") (pinfunction "1_1") (pintype "passive"))
      (node (ref "R31") (pin "1") (pinfunction "1_1") (pintype "passive"))
      (node (ref "R42") (pin "1") (pinfunction "1_1") (pintype "passive"))
      (node (ref "REG2") (pin "5") (pinfunction "VREF_5") (pintype "output"))
    )
    (net (code "148") (name "unconnected-(REG2-NC-Pad1)") (class "Default")
      (node (ref "REG2") (pin "1") (pinfunction "NC_1") (pintype "no_connect"))
    )
    (net (code "149") (name "unconnected-(RL1-PadNC1)") (class "Default")
      (node (ref "RL1") (pin "NC1") (pinfunction "NC1_NC1") (pintype "no_connect"))
    )
    (net (code "150") (name "unconnected-(RL1-PadNC2)") (class "Default")
      (node (ref "RL1") (pin "NC2") (pinfunction "NC2_NC2") (pintype "no_connect"))
    )
    (net (code "151") (name "unconnected-(RL2-PadNC1)") (class "Default")
      (node (ref "RL2") (pin "NC1") (pinfunction "NC1_NC1") (pintype "no_connect"))
    )
    (net (code "152") (name "unconnected-(RL2-PadNC2)") (class "Default")
      (node (ref "RL2") (pin "NC2") (pinfunction "NC2_NC2") (pintype "no_connect"))
    )
    (net (code "153") (name "unconnected-(RL3-PadNC1)") (class "Default")
      (node (ref "RL3") (pin "NC1") (pinfunction "NC1_NC1") (pintype "no_connect"))
    )
    (net (code "154") (name "unconnected-(RL3-PadNC2)") (class "Default")
      (node (ref "RL3") (pin "NC2") (pinfunction "NC2_NC2") (pintype "no_connect"))
    )
    (net (code "155") (name "unconnected-(RL4-PadNC1)") (class "Default")
      (node (ref "RL4") (pin "NC1") (pinfunction "NC1_NC1") (pintype "no_connect"))
    )
    (net (code "156") (name "unconnected-(RL4-PadNC2)") (class "Default")
      (node (ref "RL4") (pin "NC2") (pinfunction "NC2_NC2") (pintype "no_connect"))
    )
    (net (code "157") (name "unconnected-(RL5-PadNC1)") (class "Default")
      (node (ref "RL5") (pin "NC1") (pinfunction "NC1_NC1") (pintype "no_connect"))
    )
    (net (code "158") (name "unconnected-(RL5-PadNC2)") (class "Default")
      (node (ref "RL5") (pin "NC2") (pinfunction "NC2_NC2") (pintype "no_connect"))
    )
    (net (code "159") (name "unconnected-(RL6-PadNC1)") (class "Default")
      (node (ref "RL6") (pin "NC1") (pinfunction "NC1_NC1") (pintype "no_connect"))
    )
    (net (code "160") (name "unconnected-(RL6-PadNC2)") (class "Default")
      (node (ref "RL6") (pin "NC2") (pinfunction "NC2_NC2") (pintype "no_connect"))
    )
    (net (code "161") (name "unconnected-(RL7-PadNC1)") (class "Default")
      (node (ref "RL7") (pin "NC1") (pinfunction "NC1_NC1") (pintype "no_connect"))
    )
    (net (code "162") (name "unconnected-(RL7-PadNC2)") (class "Default")
      (node (ref "RL7") (pin "NC2") (pinfunction "NC2_NC2") (pintype "no_connect"))
    )
    (net (code "163") (name "unconnected-(RL8-PadNC1)") (class "Default")
      (node (ref "RL8") (pin "NC1") (pinfunction "NC1_NC1") (pintype "no_connect"))
    )
    (net (code "164") (name "unconnected-(RL8-PadNC2)") (class "Default")
      (node (ref "RL8") (pin "NC2") (pinfunction "NC2_NC2") (pintype "no_connect"))
    )
    (net (code "165") (name "unconnected-(U$1-Pad1)") (class "Default")
      (node (ref "U$1") (pin "1") (pinfunction "1_1") (pintype "passive"))
    )
    (net (code "166") (name "unconnected-(U$1-Pad2)") (class "Default")
      (node (ref "U$1") (pin "2") (pinfunction "2_2") (pintype "passive"))
    )
    (net (code "167") (name "unconnected-(U2-IND-Pad6)") (class "Default")
      (node (ref "U2") (pin "6") (pinfunction "IND_6") (pintype "passive"))
    )
    (net (code "168") (name "unconnected-(U2-NC-Pad7)") (class "Default")
      (node (ref "U2") (pin "7") (pinfunction "NC_7") (pintype "no_connect"))
    )
    (net (code "169") (name "unconnected-(U2-OUTD-Pad11)") (class "Default")
      (node (ref "U2") (pin "11") (pinfunction "OUTD_11") (pintype "tri_state"))
    )
    (net (code "170") (name "unconnected-(U7A--IN-Pad2)") (class "Default")
      (node (ref "U7") (pin "2") (pinfunction "-IN_2") (pintype "input"))
    )
    (net (code "171") (name "unconnected-(UC1-12{slash}MISO-Pad12)") (class "Default")
      (node (ref "UC1") (pin "12") (pinfunction "12/MISO_12") (pintype "bidirectional"))
    )
    (net (code "172") (name "unconnected-(UC1-15{slash}A1{slash}T-Pad15{slash}A1)") (class "Default")
      (node (ref "UC1") (pin "15/A1") (pinfunction "15/A1/T_15/A1") (pintype "bidirectional"))
    )
    (net (code "173") (name "unconnected-(UC1-16{slash}A2{slash}T-Pad16{slash}A2)") (class "Default")
      (node (ref "UC1") (pin "16/A2") (pinfunction "16/A2/T_16/A2") (pintype "bidirectional"))
    )
    (net (code "174") (name "unconnected-(UC1-17{slash}A3{slash}T-Pad17{slash}A3)") (class "Default")
      (node (ref "UC1") (pin "17/A3") (pinfunction "17/A3/T_17/A3") (pintype "bidirectional"))
    )
    (net (code "175") (name "unconnected-(UC1-20{slash}A6{slash}PWM-Pad20{slash}A6)") (class "Default")
      (node (ref "UC1") (pin "20/A6") (pinfunction "20/A6/PWM_20/A6") (pintype "bidirectional"))
    )
    (net (code "176") (name "unconnected-(UC1-21{slash}A7{slash}PWM-Pad21{slash}A7)") (class "Default")
      (node (ref "UC1") (pin "21/A7") (pinfunction "21/A7/PWM_21/A7") (pintype "bidirectional"))
    )
    (net (code "177") (name "unconnected-(UC1-22{slash}A8{slash}T{slash}PWM-Pad22{slash}A8)") (class "Default")
      (node (ref "UC1") (pin "22/A8") (pinfunction "22/A8/T/PWM_22/A8") (pintype "bidirectional"))
    )
    (net (code "178") (name "unconnected-(UC1-23{slash}A9{slash}T{slash}PWM-Pad23{slash}A9)") (class "Default")
      (node (ref "UC1") (pin "23/A9") (pinfunction "23/A9/T/PWM_23/A9") (pintype "bidirectional"))
    )
    (net (code "179") (name "unconnected-(UC1-Pad14{slash}A0)") (class "Default")
      (node (ref "UC1") (pin "14/A0") (pinfunction "14/A0_14/A0") (pintype "bidirectional"))
    )
    (net (code "180") (name "unconnected-(VR9-WIPER-Pad2)") (class "Default")
      (node (ref "VR9") (pin "2") (pinfunction "WIPER_2") (pintype "passive"))
    )
    (net (code "181") (name "~{SYNC_ISO}") (class "Default")
      (node (ref "DAC1") (pin "9") (pinfunction "~{SYNC}_9") (pintype "input"))
      (node (ref "U2") (pin "13") (pinfunction "OUTB_13") (pintype "tri_state"))
    )
    (net (code "182") (name "~{SYNC}") (class "Default")
      (node (ref "U2") (pin "4") (pinfunction "INB_4") (pintype "passive"))
      (node (ref "UC1") (pin "10") (pinfunction "10/TX2/PWM_10") (pintype "bidirectional"))
    )
  )
)
